# Sheet_1.net
KiCad netlist of a schematic drawn in Altium Designer
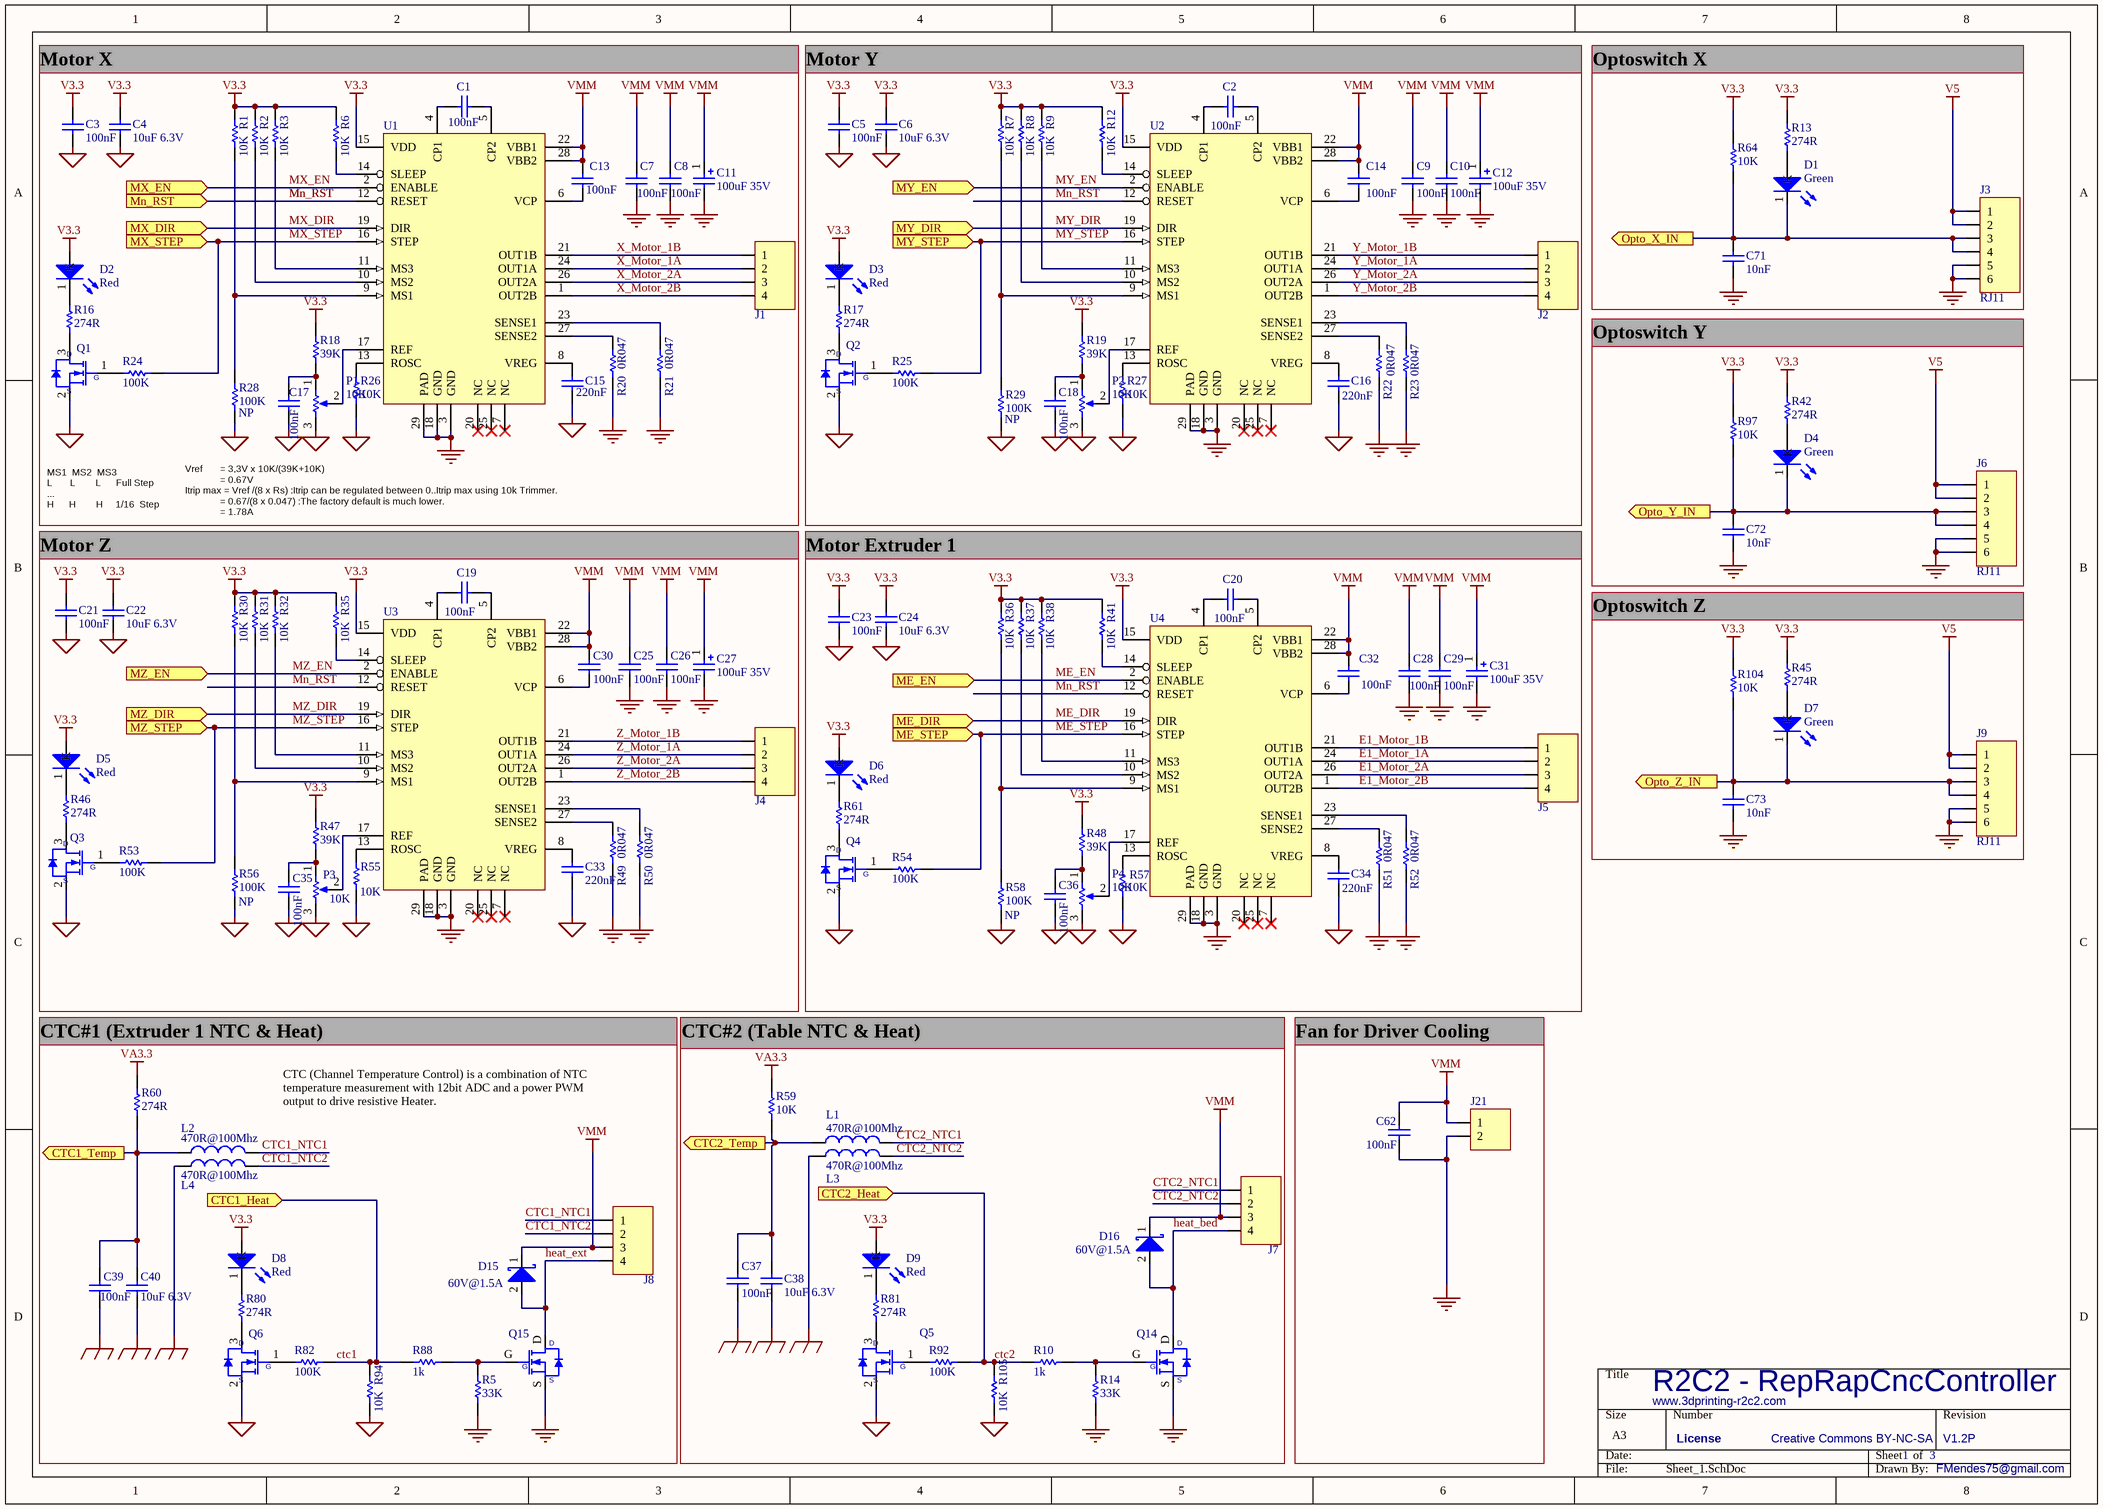
[diagram p0: Sheet_1.SchDoc]

(export (version "E")
  (design (tool "Eeschema 10.0.6"))
  (components
    (comp (ref "C1")
      (value "100nF")
      (footprint "CAPC1608M")
      (description "CAP CER 0.1UF 50V Y5V 0603")
      (fields (field (name "MANUFACTURER") "Yageo"))
      (libsource (lib "HB_DB_Components") (part "Cap Non Pol"))
    )
    (comp (ref "C2")
      (value "100nF")
      (footprint "CAPC1608M")
      (description "CAP CER 0.1UF 50V Y5V 0603")
      (fields (field (name "MANUFACTURER") "Yageo"))
      (libsource (lib "HB_DB_Components") (part "Cap Non Pol"))
    )
    (comp (ref "C3")
      (value "100nF")
      (footprint "CAPC1608M")
      (description "CAP CER 0.1UF 50V Y5V 0603")
      (fields (field (name "MANUFACTURER") "Yageo"))
      (libsource (lib "HB_DB_Components") (part "Cap Non Pol"))
    )
    (comp (ref "C4")
      (value "10uF 6.3V")
      (footprint "CAPC2012M")
      (description "CAP CER 10UF 10V Y5V 0805")
      (fields (field (name "MANUFACTURER") "Yageo"))
      (libsource (lib "HB_DB_Components") (part "Cap Non Pol"))
    )
    (comp (ref "C5")
      (value "100nF")
      (footprint "CAPC1608M")
      (description "CAP CER 0.1UF 50V Y5V 0603")
      (fields (field (name "MANUFACTURER") "Yageo"))
      (libsource (lib "HB_DB_Components") (part "Cap Non Pol"))
    )
    (comp (ref "C6")
      (value "10uF 6.3V")
      (footprint "CAPC2012M")
      (description "CAP CER 10UF 10V Y5V 0805")
      (fields (field (name "MANUFACTURER") "Yageo"))
      (libsource (lib "HB_DB_Components") (part "Cap Non Pol"))
    )
    (comp (ref "C7")
      (value "100nF")
      (footprint "CAPC1608M")
      (description "CAP CER 0.1UF 50V Y5V 0603")
      (fields (field (name "MANUFACTURER") "Yageo"))
      (libsource (lib "HB_DB_Components") (part "Cap Non Pol"))
    )
    (comp (ref "C8")
      (value "100nF")
      (footprint "CAPC1608M")
      (description "CAP CER 0.1UF 50V Y5V 0603")
      (fields (field (name "MANUFACTURER") "Yageo"))
      (libsource (lib "HB_DB_Components") (part "Cap Non Pol"))
    )
    (comp (ref "C9")
      (value "100nF")
      (footprint "CAPC1608M")
      (description "CAP CER 0.1UF 50V Y5V 0603")
      (fields (field (name "MANUFACTURER") "Yageo"))
      (libsource (lib "HB_DB_Components") (part "Cap Non Pol"))
    )
    (comp (ref "C10")
      (value "100nF")
      (footprint "CAPC1608M")
      (description "CAP CER 0.1UF 50V Y5V 0603")
      (fields (field (name "MANUFACTURER") "Yageo"))
      (libsource (lib "HB_DB_Components") (part "Cap Non Pol"))
    )
    (comp (ref "C11")
      (value "100uF 35V")
      (footprint "CAPAE63x63MM")
      (description "CAP ALUM 100UF 35V 20% SMD")
      (fields (field (name "MANUFACTURER") "Panasonic"))
      (libsource (lib "HB_DB_Components") (part "Cap Pol"))
    )
    (comp (ref "C12")
      (value "100uF 35V")
      (footprint "CAPAE63x63MM")
      (description "CAP ALUM 100UF 35V 20% SMD")
      (fields (field (name "MANUFACTURER") "Panasonic"))
      (libsource (lib "HB_DB_Components") (part "Cap Pol"))
    )
    (comp (ref "C13")
      (value "100nF")
      (footprint "CAPC1608M")
      (description "CAP CER 0.1UF 50V Y5V 0603")
      (fields (field (name "MANUFACTURER") "Yageo"))
      (libsource (lib "HB_DB_Components") (part "Cap Non Pol"))
    )
    (comp (ref "C14")
      (value "100nF")
      (footprint "CAPC1608M")
      (description "CAP CER 0.1UF 50V Y5V 0603")
      (fields (field (name "MANUFACTURER") "Yageo"))
      (libsource (lib "HB_DB_Components") (part "Cap Non Pol"))
    )
    (comp (ref "C15")
      (value "220nF")
      (footprint "CAPC1608M")
      (description "CAP CER 0.22UF 16V 10% X7R 0603")
      (fields (field (name "MANUFACTURER") "TDK"))
      (libsource (lib "HB_DB_Components") (part "Cap Non Pol"))
    )
    (comp (ref "C16")
      (value "220nF")
      (footprint "CAPC1608M")
      (description "CAP CER 0.22UF 16V 10% X7R 0603")
      (fields (field (name "MANUFACTURER") "TDK"))
      (libsource (lib "HB_DB_Components") (part "Cap Non Pol"))
    )
    (comp (ref "C17")
      (value "100nF")
      (footprint "CAPC1608M")
      (description "CAP CER 0.1UF 50V Y5V 0603")
      (fields (field (name "MANUFACTURER") "Yageo"))
      (libsource (lib "HB_DB_Components") (part "Cap Non Pol"))
    )
    (comp (ref "C18")
      (value "100nF")
      (footprint "CAPC1608M")
      (description "CAP CER 0.1UF 50V Y5V 0603")
      (fields (field (name "MANUFACTURER") "Yageo"))
      (libsource (lib "HB_DB_Components") (part "Cap Non Pol"))
    )
    (comp (ref "C19")
      (value "100nF")
      (footprint "CAPC1608M")
      (description "CAP CER 0.1UF 50V Y5V 0603")
      (fields (field (name "MANUFACTURER") "Yageo"))
      (libsource (lib "HB_DB_Components") (part "Cap Non Pol"))
    )
    (comp (ref "C20")
      (value "100nF")
      (footprint "CAPC1608M")
      (description "CAP CER 0.1UF 50V Y5V 0603")
      (fields (field (name "MANUFACTURER") "Yageo"))
      (libsource (lib "HB_DB_Components") (part "Cap Non Pol"))
    )
    (comp (ref "C21")
      (value "100nF")
      (footprint "CAPC1608M")
      (description "CAP CER 0.1UF 50V Y5V 0603")
      (fields (field (name "MANUFACTURER") "Yageo"))
      (libsource (lib "HB_DB_Components") (part "Cap Non Pol"))
    )
    (comp (ref "C22")
      (value "10uF 6.3V")
      (footprint "CAPC2012M")
      (description "CAP CER 10UF 10V Y5V 0805")
      (fields (field (name "MANUFACTURER") "Yageo"))
      (libsource (lib "HB_DB_Components") (part "Cap Non Pol"))
    )
    (comp (ref "C23")
      (value "100nF")
      (footprint "CAPC1608M")
      (description "CAP CER 0.1UF 50V Y5V 0603")
      (fields (field (name "MANUFACTURER") "Yageo"))
      (libsource (lib "HB_DB_Components") (part "Cap Non Pol"))
    )
    (comp (ref "C24")
      (value "10uF 6.3V")
      (footprint "CAPC2012M")
      (description "CAP CER 10UF 10V Y5V 0805")
      (fields (field (name "MANUFACTURER") "Yageo"))
      (libsource (lib "HB_DB_Components") (part "Cap Non Pol"))
    )
    (comp (ref "C25")
      (value "100nF")
      (footprint "CAPC1608M")
      (description "CAP CER 0.1UF 50V Y5V 0603")
      (fields (field (name "MANUFACTURER") "Yageo"))
      (libsource (lib "HB_DB_Components") (part "Cap Non Pol"))
    )
    (comp (ref "C26")
      (value "100nF")
      (footprint "CAPC1608M")
      (description "CAP CER 0.1UF 50V Y5V 0603")
      (fields (field (name "MANUFACTURER") "Yageo"))
      (libsource (lib "HB_DB_Components") (part "Cap Non Pol"))
    )
    (comp (ref "C27")
      (value "100uF 35V")
      (footprint "CAPAE63x63MM")
      (description "CAP ALUM 100UF 35V 20% SMD")
      (fields (field (name "MANUFACTURER") "Panasonic"))
      (libsource (lib "HB_DB_Components") (part "Cap Pol"))
    )
    (comp (ref "C28")
      (value "100nF")
      (footprint "CAPC1608M")
      (description "CAP CER 0.1UF 50V Y5V 0603")
      (fields (field (name "MANUFACTURER") "Yageo"))
      (libsource (lib "HB_DB_Components") (part "Cap Non Pol"))
    )
    (comp (ref "C29")
      (value "100nF")
      (footprint "CAPC1608M")
      (description "CAP CER 0.1UF 50V Y5V 0603")
      (fields (field (name "MANUFACTURER") "Yageo"))
      (libsource (lib "HB_DB_Components") (part "Cap Non Pol"))
    )
    (comp (ref "C30")
      (value "100nF")
      (footprint "CAPC1608M")
      (description "CAP CER 0.1UF 50V Y5V 0603")
      (fields (field (name "MANUFACTURER") "Yageo"))
      (libsource (lib "HB_DB_Components") (part "Cap Non Pol"))
    )
    (comp (ref "C31")
      (value "100uF 35V")
      (footprint "CAPAE63x63MM")
      (description "CAP ALUM 100UF 35V 20% SMD")
      (fields (field (name "MANUFACTURER") "Panasonic"))
      (libsource (lib "HB_DB_Components") (part "Cap Pol"))
    )
    (comp (ref "C32")
      (value "100nF")
      (footprint "CAPC1608M")
      (description "CAP CER 0.1UF 50V Y5V 0603")
      (fields (field (name "MANUFACTURER") "Yageo"))
      (libsource (lib "HB_DB_Components") (part "Cap Non Pol"))
    )
    (comp (ref "C33")
      (value "220nF")
      (footprint "CAPC1608M")
      (description "CAP CER 0.22UF 16V 10% X7R 0603")
      (fields (field (name "MANUFACTURER") "TDK"))
      (libsource (lib "HB_DB_Components") (part "Cap Non Pol"))
    )
    (comp (ref "C34")
      (value "220nF")
      (footprint "CAPC1608M")
      (description "CAP CER 0.22UF 16V 10% X7R 0603")
      (fields (field (name "MANUFACTURER") "TDK"))
      (libsource (lib "HB_DB_Components") (part "Cap Non Pol"))
    )
    (comp (ref "C35")
      (value "100nF")
      (footprint "CAPC1608M")
      (description "CAP CER 0.1UF 50V Y5V 0603")
      (fields (field (name "MANUFACTURER") "Yageo"))
      (libsource (lib "HB_DB_Components") (part "Cap Non Pol"))
    )
    (comp (ref "C36")
      (value "100nF")
      (footprint "CAPC1608M")
      (description "CAP CER 0.1UF 50V Y5V 0603")
      (fields (field (name "MANUFACTURER") "Yageo"))
      (libsource (lib "HB_DB_Components") (part "Cap Non Pol"))
    )
    (comp (ref "C37")
      (value "100nF")
      (footprint "CAPC1608M")
      (description "CAP CER 0.1UF 50V Y5V 0603")
      (fields (field (name "MANUFACTURER") "Yageo"))
      (libsource (lib "HB_DB_Components") (part "Cap Non Pol"))
    )
    (comp (ref "C38")
      (value "10uF 6.3V")
      (footprint "CAPC2012M")
      (description "CAP CER 10UF 10V Y5V 0805")
      (fields (field (name "MANUFACTURER") "Yageo"))
      (libsource (lib "HB_DB_Components") (part "Cap Non Pol"))
    )
    (comp (ref "C39")
      (value "100nF")
      (footprint "CAPC1608M")
      (description "CAP CER 0.1UF 50V Y5V 0603")
      (fields (field (name "MANUFACTURER") "Yageo"))
      (libsource (lib "HB_DB_Components") (part "Cap Non Pol"))
    )
    (comp (ref "C40")
      (value "10uF 6.3V")
      (footprint "CAPC2012M")
      (description "CAP CER 10UF 10V Y5V 0805")
      (fields (field (name "MANUFACTURER") "Yageo"))
      (libsource (lib "HB_DB_Components") (part "Cap Non Pol"))
    )
    (comp (ref "C62")
      (value "100nF")
      (footprint "CAPC1608M")
      (description "CAP CER 0.1UF 50V Y5V 0603")
      (fields (field (name "MANUFACTURER") "Yageo"))
      (libsource (lib "HB_DB_Components") (part "Cap Non Pol"))
    )
    (comp (ref "C71")
      (value "10nF")
      (footprint "CAPC1608M")
      (description "CAP CER 10000PF 50V 10% X7R 0603")
      (fields (field (name "MANUFACTURER") "TDK"))
      (libsource (lib "HB_DB_Components") (part "Cap Non Pol"))
    )
    (comp (ref "C72")
      (value "10nF")
      (footprint "CAPC1608M")
      (description "CAP CER 10000PF 50V 10% X7R 0603")
      (fields (field (name "MANUFACTURER") "TDK"))
      (libsource (lib "HB_DB_Components") (part "Cap Non Pol"))
    )
    (comp (ref "C73")
      (value "10nF")
      (footprint "CAPC1608M")
      (description "CAP CER 10000PF 50V 10% X7R 0603")
      (fields (field (name "MANUFACTURER") "TDK"))
      (libsource (lib "HB_DB_Components") (part "Cap Non Pol"))
    )
    (comp (ref "D1")
      (value "Green")
      (footprint "LEDM_3216X12M")
      (description "LED CHIPLED 570NM GREEN 1206 SMD")
      (fields (field (name "MANUFACTURER") "OSRAM"))
      (libsource (lib "altium-import") (part "root_3_LED_"))
    )
    (comp (ref "D2")
      (value "Red")
      (footprint "LEDM_3216X12M")
      (description "LED CHIPLED 645NM RED DIFF 1206")
      (fields (field (name "MANUFACTURER") "OSRAM"))
      (libsource (lib "HB_DB_Components") (part "LED"))
    )
    (comp (ref "D3")
      (value "Red")
      (footprint "LEDM_3216X12M")
      (description "LED CHIPLED 645NM RED DIFF 1206")
      (fields (field (name "MANUFACTURER") "OSRAM"))
      (libsource (lib "HB_DB_Components") (part "LED"))
    )
    (comp (ref "D4")
      (value "Green")
      (footprint "LEDM_3216X12M")
      (description "LED CHIPLED 570NM GREEN 1206 SMD")
      (fields (field (name "MANUFACTURER") "OSRAM"))
      (libsource (lib "altium-import") (part "root_3_LED_"))
    )
    (comp (ref "D5")
      (value "Red")
      (footprint "LEDM_3216X12M")
      (description "LED CHIPLED 645NM RED DIFF 1206")
      (fields (field (name "MANUFACTURER") "OSRAM"))
      (libsource (lib "HB_DB_Components") (part "LED"))
    )
    (comp (ref "D6")
      (value "Red")
      (footprint "LEDM_3216X12M")
      (description "LED CHIPLED 645NM RED DIFF 1206")
      (fields (field (name "MANUFACTURER") "OSRAM"))
      (libsource (lib "HB_DB_Components") (part "LED"))
    )
    (comp (ref "D7")
      (value "Green")
      (footprint "LEDM_3216X12M")
      (description "LED CHIPLED 570NM GREEN 1206 SMD")
      (fields (field (name "MANUFACTURER") "OSRAM"))
      (libsource (lib "altium-import") (part "root_3_LED_"))
    )
    (comp (ref "D8")
      (value "Red")
      (footprint "LEDM_3216X12M")
      (description "LED CHIPLED 645NM RED DIFF 1206")
      (fields (field (name "MANUFACTURER") "OSRAM"))
      (libsource (lib "HB_DB_Components") (part "LED"))
    )
    (comp (ref "D9")
      (value "Red")
      (footprint "LEDM_3216X12M")
      (description "LED CHIPLED 645NM RED DIFF 1206")
      (fields (field (name "MANUFACTURER") "OSRAM"))
      (libsource (lib "HB_DB_Components") (part "LED"))
    )
    (comp (ref "D15")
      (value "60V@1.5A")
      (footprint "SMA")
      (description "DIODE SCHOTTKY 60V 2.1A DO214AC")
      (fields (field (name "MANUFACTURER") "VISHAY"))
      (libsource (lib "HB_DB_Components") (part "D Schottky"))
    )
    (comp (ref "D16")
      (value "60V@1.5A")
      (footprint "SMA")
      (description "DIODE SCHOTTKY 60V 2.1A DO214AC")
      (fields (field (name "MANUFACTURER") "VISHAY"))
      (libsource (lib "HB_DB_Components") (part "D Schottky"))
    )
    (comp (ref "J1")
      (value "~")
      (footprint "TE_SCREW_1X4")
      (description "Con 4")
      (fields (field (name "MANUFACTURER") "TE"))
      (libsource (lib "HB_DB_Components") (part "Con 4"))
    )
    (comp (ref "J2")
      (value "~")
      (footprint "TE_SCREW_1X4")
      (description "Con 4")
      (fields (field (name "MANUFACTURER") "TE"))
      (libsource (lib "HB_DB_Components") (part "Con 4"))
    )
    (comp (ref "J3")
      (value "RJ11")
      (footprint "MOLEX_95022-2667")
      (description "CONN MOD JACK R/A 6P4C")
      (fields (field (name "MANUFACTURER") "Stewart Connector"))
      (libsource (lib "HB_DB_Components") (part "Con 6"))
    )
    (comp (ref "J4")
      (value "~")
      (footprint "TE_SCREW_1X4")
      (description "Con 4")
      (fields (field (name "MANUFACTURER") "TE"))
      (libsource (lib "HB_DB_Components") (part "Con 4"))
    )
    (comp (ref "J5")
      (value "~")
      (footprint "TE_SCREW_1X4")
      (description "Con 4")
      (fields (field (name "MANUFACTURER") "TE"))
      (libsource (lib "HB_DB_Components") (part "Con 4"))
    )
    (comp (ref "J6")
      (value "RJ11")
      (footprint "MOLEX_95022-2667")
      (description "CONN MOD JACK R/A 6P4C")
      (fields (field (name "MANUFACTURER") "Stewart Connector"))
      (libsource (lib "HB_DB_Components") (part "Con 6"))
    )
    (comp (ref "J7")
      (value "~")
      (footprint "TE_SCREW_282841-4")
      (description "Con 4")
      (fields (field (name "MANUFACTURER") "TE"))
      (libsource (lib "HB_DB_Components") (part "Con 4"))
    )
    (comp (ref "J8")
      (value "~")
      (footprint "TE_SCREW_282841-4")
      (description "Con 4")
      (fields (field (name "MANUFACTURER") "TE"))
      (libsource (lib "HB_DB_Components") (part "Con 4"))
    )
    (comp (ref "J9")
      (value "RJ11")
      (footprint "MOLEX_95022-2667")
      (description "CONN MOD JACK R/A 6P4C")
      (fields (field (name "MANUFACTURER") "Stewart Connector"))
      (libsource (lib "HB_DB_Components") (part "Con 6"))
    )
    (comp (ref "J21")
      (value "-")
      (footprint "MOLEX_22-29-2021")
      (description "CONN HEADER 2POS .100 VERT GOLD")
      (fields (field (name "MANUFACTURER") "Molex"))
      (libsource (lib "HB_DB_Components") (part "Con 2"))
    )
    (comp (ref "L1")
      (value "470R@100Mhz")
      (footprint "INDC1608M")
      (description "FERRITE CHIP 470 OHM 1000MA 0603")
      (fields (field (name "MANUFACTURER") "MURATA"))
      (libsource (lib "HB_DB_Components") (part "Ind"))
    )
    (comp (ref "L2")
      (value "470R@100Mhz")
      (footprint "INDC1608M")
      (description "FERRITE CHIP 470 OHM 1000MA 0603")
      (fields (field (name "MANUFACTURER") "MURATA"))
      (libsource (lib "HB_DB_Components") (part "Ind"))
    )
    (comp (ref "L3")
      (value "470R@100Mhz")
      (footprint "INDC1608M")
      (description "FERRITE CHIP 470 OHM 1000MA 0603")
      (fields (field (name "MANUFACTURER") "MURATA"))
      (libsource (lib "HB_DB_Components") (part "Ind"))
    )
    (comp (ref "L4")
      (value "470R@100Mhz")
      (footprint "INDC1608M")
      (description "FERRITE CHIP 470 OHM 1000MA 0603")
      (fields (field (name "MANUFACTURER") "MURATA"))
      (libsource (lib "HB_DB_Components") (part "Ind"))
    )
    (comp (ref "P1")
      (value "10K")
      (footprint "Trimmer_14")
      (description "TRIMMER 10K OHM 0.5W TH")
      (fields (field (name "MANUFACTURER") "copal"))
      (libsource (lib "HB_DB_Components") (part "Res Pot"))
    )
    (comp (ref "P2")
      (value "10K")
      (footprint "Trimmer_14")
      (description "TRIMMER 10K OHM 0.5W TH")
      (fields (field (name "MANUFACTURER") "copal"))
      (libsource (lib "HB_DB_Components") (part "Res Pot"))
    )
    (comp (ref "P3")
      (value "10K")
      (footprint "Trimmer_14")
      (description "TRIMMER 10K OHM 0.5W TH")
      (fields (field (name "MANUFACTURER") "copal"))
      (libsource (lib "HB_DB_Components") (part "Res Pot"))
    )
    (comp (ref "P4")
      (value "10K")
      (footprint "Trimmer_14")
      (description "TRIMMER 10K OHM 0.5W TH")
      (fields (field (name "MANUFACTURER") "copal"))
      (libsource (lib "HB_DB_Components") (part "Res Pot"))
    )
    (comp (ref "Q1")
      (value "~")
      (footprint "SOT323-3AM")
      (description "MOSFET N-CH SGL 60V SOT-323")
      (fields (field (name "MANUFACTURER") "NXP"))
      (libsource (lib "") (part "Q MOSFET-N_1"))
    )
    (comp (ref "Q2")
      (value "~")
      (footprint "SOT323-3AM")
      (description "MOSFET N-CH SGL 60V SOT-323")
      (fields (field (name "MANUFACTURER") "NXP"))
      (libsource (lib "") (part "Q MOSFET-N_1"))
    )
    (comp (ref "Q3")
      (value "~")
      (footprint "SOT323-3AM")
      (description "MOSFET N-CH SGL 60V SOT-323")
      (fields (field (name "MANUFACTURER") "NXP"))
      (libsource (lib "") (part "Q MOSFET-N_1"))
    )
    (comp (ref "Q4")
      (value "~")
      (footprint "SOT323-3AM")
      (description "MOSFET N-CH SGL 60V SOT-323")
      (fields (field (name "MANUFACTURER") "NXP"))
      (libsource (lib "") (part "Q MOSFET-N_1"))
    )
    (comp (ref "Q5")
      (value "~")
      (footprint "SOT323-3AM")
      (description "MOSFET N-CH SGL 60V SOT-323")
      (fields (field (name "MANUFACTURER") "NXP"))
      (libsource (lib "") (part "Q MOSFET-N_1"))
    )
    (comp (ref "Q6")
      (value "~")
      (footprint "SOT323-3AM")
      (description "MOSFET N-CH SGL 60V SOT-323")
      (fields (field (name "MANUFACTURER") "NXP"))
      (libsource (lib "") (part "Q MOSFET-N_1"))
    )
    (comp (ref "Q14")
      (value "~")
      (footprint "SuperSOP8_csd17301")
      (description "MOSFET N-CH 30V 28A 8SON")
      (fields (field (name "MANUFACTURER") "Texas Instruments"))
      (libsource (lib "HB_DB_Components") (part "Q MOSFET-N"))
    )
    (comp (ref "Q15")
      (value "~")
      (footprint "SuperSOP8_csd17301")
      (description "MOSFET N-CH 30V 28A 8SON")
      (fields (field (name "MANUFACTURER") "Texas Instruments"))
      (libsource (lib "HB_DB_Components") (part "Q MOSFET-N"))
    )
    (comp (ref "R1")
      (value "10K")
      (footprint "RESC1608M")
      (description "RES 10K OHM 1/10W 5% 0603 SMD")
      (fields (field (name "MANUFACTURER") "Yageo"))
      (libsource (lib "HB_DB_Components") (part "Res"))
    )
    (comp (ref "R2")
      (value "10K")
      (footprint "RESC1608M")
      (description "RES 10K OHM 1/10W 5% 0603 SMD")
      (fields (field (name "MANUFACTURER") "Yageo"))
      (libsource (lib "HB_DB_Components") (part "Res"))
    )
    (comp (ref "R3")
      (value "10K")
      (footprint "RESC1608M")
      (description "RES 10K OHM 1/10W 5% 0603 SMD")
      (fields (field (name "MANUFACTURER") "Yageo"))
      (libsource (lib "HB_DB_Components") (part "Res"))
    )
    (comp (ref "R5")
      (value "33K")
      (footprint "RESC1608M")
      (description "RES 33K OHM 1/10W 1% 0603")
      (fields (field (name "MANUFACTURER") "Stackpole Electronics Inc"))
      (libsource (lib "HB_DB_Components") (part "Res"))
    )
    (comp (ref "R6")
      (value "10K")
      (footprint "RESC1608M")
      (description "RES 10K OHM 1/10W 5% 0603 SMD")
      (fields (field (name "MANUFACTURER") "Yageo"))
      (libsource (lib "HB_DB_Components") (part "Res"))
    )
    (comp (ref "R7")
      (value "10K")
      (footprint "RESC1608M")
      (description "RES 10K OHM 1/10W 5% 0603 SMD")
      (fields (field (name "MANUFACTURER") "Yageo"))
      (libsource (lib "HB_DB_Components") (part "Res"))
    )
    (comp (ref "R8")
      (value "10K")
      (footprint "RESC1608M")
      (description "RES 10K OHM 1/10W 5% 0603 SMD")
      (fields (field (name "MANUFACTURER") "Yageo"))
      (libsource (lib "HB_DB_Components") (part "Res"))
    )
    (comp (ref "R9")
      (value "10K")
      (footprint "RESC1608M")
      (description "RES 10K OHM 1/10W 5% 0603 SMD")
      (fields (field (name "MANUFACTURER") "Yageo"))
      (libsource (lib "HB_DB_Components") (part "Res"))
    )
    (comp (ref "R10")
      (value "1k")
      (footprint "RESC1608M")
      (description "RES 1K OHM 1/10W 5% 0603")
      (fields (field (name "MANUFACTURER") "Stackpole Electronics Inc"))
      (libsource (lib "HB_DB_Components") (part "Res"))
    )
    (comp (ref "R12")
      (value "10K")
      (footprint "RESC1608M")
      (description "RES 10K OHM 1/10W 5% 0603 SMD")
      (fields (field (name "MANUFACTURER") "Yageo"))
      (libsource (lib "HB_DB_Components") (part "Res"))
    )
    (comp (ref "R13")
      (value "274R")
      (footprint "RESC1608M")
      (description "RES 274 OHM 1/10W 1% 0603")
      (fields (field (name "MANUFACTURER") "Stackpole Electronics Inc"))
      (libsource (lib "HB_DB_Components") (part "Res"))
    )
    (comp (ref "R14")
      (value "33K")
      (footprint "RESC1608M")
      (description "RES 33K OHM 1/10W 1% 0603")
      (fields (field (name "MANUFACTURER") "Stackpole Electronics Inc"))
      (libsource (lib "HB_DB_Components") (part "Res"))
    )
    (comp (ref "R16")
      (value "274R")
      (footprint "RESC1608M")
      (description "RES 274 OHM 1/10W 1% 0603")
      (fields (field (name "MANUFACTURER") "Stackpole Electronics Inc"))
      (libsource (lib "HB_DB_Components") (part "Res"))
    )
    (comp (ref "R17")
      (value "274R")
      (footprint "RESC1608M")
      (description "RES 274 OHM 1/10W 1% 0603")
      (fields (field (name "MANUFACTURER") "Stackpole Electronics Inc"))
      (libsource (lib "HB_DB_Components") (part "Res"))
    )
    (comp (ref "R18")
      (value "39K")
      (footprint "RESC1608M")
      (description "RES 39K OHM 1/10W 1% 0603")
      (fields (field (name "MANUFACTURER") "Stackpole Electronics Inc"))
      (libsource (lib "HB_DB_Components") (part "Res"))
    )
    (comp (ref "R19")
      (value "39K")
      (footprint "RESC1608M")
      (description "RES 39K OHM 1/10W 1% 0603")
      (fields (field (name "MANUFACTURER") "Stackpole Electronics Inc"))
      (libsource (lib "HB_DB_Components") (part "Res"))
    )
    (comp (ref "R20")
      (value "0R047")
      (footprint "RESC3216M")
      (description "RES .047 OHM 1/2W 1% 1206 SMD")
      (fields (field (name "MANUFACTURER") "Ohmite"))
      (libsource (lib "HB_DB_Components") (part "Res"))
    )
    (comp (ref "R21")
      (value "0R047")
      (footprint "RESC3216M")
      (description "RES .047 OHM 1/2W 1% 1206 SMD")
      (fields (field (name "MANUFACTURER") "Ohmite"))
      (libsource (lib "HB_DB_Components") (part "Res"))
    )
    (comp (ref "R22")
      (value "0R047")
      (footprint "RESC3216M")
      (description "RES .047 OHM 1/2W 1% 1206 SMD")
      (fields (field (name "MANUFACTURER") "Ohmite"))
      (libsource (lib "HB_DB_Components") (part "Res"))
    )
    (comp (ref "R23")
      (value "0R047")
      (footprint "RESC3216M")
      (description "RES .047 OHM 1/2W 1% 1206 SMD")
      (fields (field (name "MANUFACTURER") "Ohmite"))
      (libsource (lib "HB_DB_Components") (part "Res"))
    )
    (comp (ref "R24")
      (value "100K")
      (footprint "RESC1608M")
      (description "RES 100K OHM 1/10W 5% 0603 SMD")
      (fields (field (name "MANUFACTURER") "Yageo"))
      (libsource (lib "HB_DB_Components") (part "Res"))
    )
    (comp (ref "R25")
      (value "100K")
      (footprint "RESC1608M")
      (description "RES 100K OHM 1/10W 5% 0603 SMD")
      (fields (field (name "MANUFACTURER") "Yageo"))
      (libsource (lib "HB_DB_Components") (part "Res"))
    )
    (comp (ref "R26")
      (value "10K")
      (footprint "RESC1608M")
      (description "RES 10K OHM 1/10W 5% 0603 SMD")
      (fields (field (name "MANUFACTURER") "Yageo"))
      (libsource (lib "HB_DB_Components") (part "Res"))
    )
    (comp (ref "R27")
      (value "10K")
      (footprint "RESC1608M")
      (description "RES 10K OHM 1/10W 5% 0603 SMD")
      (fields (field (name "MANUFACTURER") "Yageo"))
      (libsource (lib "HB_DB_Components") (part "Res"))
    )
    (comp (ref "R28")
      (value "100K")
      (footprint "RESC1608M")
      (description "RES 100K OHM 1/10W 5% 0603 SMD")
      (fields (field (name "MANUFACTURER") "Yageo") (field (name "POPULATE") "NP"))
      (libsource (lib "HB_DB_Components") (part "Res"))
    )
    (comp (ref "R29")
      (value "100K")
      (footprint "RESC1608M")
      (description "RES 100K OHM 1/10W 5% 0603 SMD")
      (fields (field (name "MANUFACTURER") "Yageo") (field (name "POPULATE") "NP"))
      (libsource (lib "HB_DB_Components") (part "Res"))
    )
    (comp (ref "R30")
      (value "10K")
      (footprint "RESC1608M")
      (description "RES 10K OHM 1/10W 5% 0603 SMD")
      (fields (field (name "MANUFACTURER") "Yageo"))
      (libsource (lib "HB_DB_Components") (part "Res"))
    )
    (comp (ref "R31")
      (value "10K")
      (footprint "RESC1608M")
      (description "RES 10K OHM 1/10W 5% 0603 SMD")
      (fields (field (name "MANUFACTURER") "Yageo"))
      (libsource (lib "HB_DB_Components") (part "Res"))
    )
    (comp (ref "R32")
      (value "10K")
      (footprint "RESC1608M")
      (description "RES 10K OHM 1/10W 5% 0603 SMD")
      (fields (field (name "MANUFACTURER") "Yageo"))
      (libsource (lib "HB_DB_Components") (part "Res"))
    )
    (comp (ref "R35")
      (value "10K")
      (footprint "RESC1608M")
      (description "RES 10K OHM 1/10W 5% 0603 SMD")
      (fields (field (name "MANUFACTURER") "Yageo"))
      (libsource (lib "HB_DB_Components") (part "Res"))
    )
    (comp (ref "R36")
      (value "10K")
      (footprint "RESC1608M")
      (description "RES 10K OHM 1/10W 5% 0603 SMD")
      (fields (field (name "MANUFACTURER") "Yageo"))
      (libsource (lib "HB_DB_Components") (part "Res"))
    )
    (comp (ref "R37")
      (value "10K")
      (footprint "RESC1608M")
      (description "RES 10K OHM 1/10W 5% 0603 SMD")
      (fields (field (name "MANUFACTURER") "Yageo"))
      (libsource (lib "HB_DB_Components") (part "Res"))
    )
    (comp (ref "R38")
      (value "10K")
      (footprint "RESC1608M")
      (description "RES 10K OHM 1/10W 5% 0603 SMD")
      (fields (field (name "MANUFACTURER") "Yageo"))
      (libsource (lib "HB_DB_Components") (part "Res"))
    )
    (comp (ref "R41")
      (value "10K")
      (footprint "RESC1608M")
      (description "RES 10K OHM 1/10W 5% 0603 SMD")
      (fields (field (name "MANUFACTURER") "Yageo"))
      (libsource (lib "HB_DB_Components") (part "Res"))
    )
    (comp (ref "R42")
      (value "274R")
      (footprint "RESC1608M")
      (description "RES 274 OHM 1/10W 1% 0603")
      (fields (field (name "MANUFACTURER") "Stackpole Electronics Inc"))
      (libsource (lib "HB_DB_Components") (part "Res"))
    )
    (comp (ref "R45")
      (value "274R")
      (footprint "RESC1608M")
      (description "RES 274 OHM 1/10W 1% 0603")
      (fields (field (name "MANUFACTURER") "Stackpole Electronics Inc"))
      (libsource (lib "HB_DB_Components") (part "Res"))
    )
    (comp (ref "R46")
      (value "274R")
      (footprint "RESC1608M")
      (description "RES 274 OHM 1/10W 1% 0603")
      (fields (field (name "MANUFACTURER") "Stackpole Electronics Inc"))
      (libsource (lib "HB_DB_Components") (part "Res"))
    )
    (comp (ref "R47")
      (value "39K")
      (footprint "RESC1608M")
      (description "RES 39K OHM 1/10W 1% 0603")
      (fields (field (name "MANUFACTURER") "Stackpole Electronics Inc"))
      (libsource (lib "HB_DB_Components") (part "Res"))
    )
    (comp (ref "R48")
      (value "39K")
      (footprint "RESC1608M")
      (description "RES 39K OHM 1/10W 1% 0603")
      (fields (field (name "MANUFACTURER") "Stackpole Electronics Inc"))
      (libsource (lib "HB_DB_Components") (part "Res"))
    )
    (comp (ref "R49")
      (value "0R047")
      (footprint "RESC3216M")
      (description "RES .047 OHM 1/2W 1% 1206 SMD")
      (fields (field (name "MANUFACTURER") "Ohmite"))
      (libsource (lib "HB_DB_Components") (part "Res"))
    )
    (comp (ref "R50")
      (value "0R047")
      (footprint "RESC3216M")
      (description "RES .047 OHM 1/2W 1% 1206 SMD")
      (fields (field (name "MANUFACTURER") "Ohmite"))
      (libsource (lib "HB_DB_Components") (part "Res"))
    )
    (comp (ref "R51")
      (value "0R047")
      (footprint "RESC3216M")
      (description "RES .047 OHM 1/2W 1% 1206 SMD")
      (fields (field (name "MANUFACTURER") "Ohmite"))
      (libsource (lib "HB_DB_Components") (part "Res"))
    )
    (comp (ref "R52")
      (value "0R047")
      (footprint "RESC3216M")
      (description "RES .047 OHM 1/2W 1% 1206 SMD")
      (fields (field (name "MANUFACTURER") "Ohmite"))
      (libsource (lib "HB_DB_Components") (part "Res"))
    )
    (comp (ref "R53")
      (value "100K")
      (footprint "RESC1608M")
      (description "RES 100K OHM 1/10W 5% 0603 SMD")
      (fields (field (name "MANUFACTURER") "Yageo"))
      (libsource (lib "HB_DB_Components") (part "Res"))
    )
    (comp (ref "R54")
      (value "100K")
      (footprint "RESC1608M")
      (description "RES 100K OHM 1/10W 5% 0603 SMD")
      (fields (field (name "MANUFACTURER") "Yageo"))
      (libsource (lib "HB_DB_Components") (part "Res"))
    )
    (comp (ref "R55")
      (value "10K")
      (footprint "RESC1608M")
      (description "RES 10K OHM 1/10W 5% 0603 SMD")
      (fields (field (name "MANUFACTURER") "Yageo"))
      (libsource (lib "HB_DB_Components") (part "Res"))
    )
    (comp (ref "R56")
      (value "100K")
      (footprint "RESC1608M")
      (description "RES 100K OHM 1/10W 5% 0603 SMD")
      (fields (field (name "MANUFACTURER") "Yageo") (field (name "POPULATE") "NP"))
      (libsource (lib "HB_DB_Components") (part "Res"))
    )
    (comp (ref "R57")
      (value "10K")
      (footprint "RESC1608M")
      (description "RES 10K OHM 1/10W 5% 0603 SMD")
      (fields (field (name "MANUFACTURER") "Yageo"))
      (libsource (lib "HB_DB_Components") (part "Res"))
    )
    (comp (ref "R58")
      (value "100K")
      (footprint "RESC1608M")
      (description "RES 100K OHM 1/10W 5% 0603 SMD")
      (fields (field (name "MANUFACTURER") "Yageo") (field (name "POPULATE") "NP"))
      (libsource (lib "HB_DB_Components") (part "Res"))
    )
    (comp (ref "R59")
      (value "10K")
      (footprint "RESC1608M")
      (description "RES 10K OHM 1/10W 5% 0603 SMD")
      (fields (field (name "MANUFACTURER") "Yageo"))
      (libsource (lib "HB_DB_Components") (part "Res"))
    )
    (comp (ref "R60")
      (value "274R")
      (footprint "RESC1608M")
      (description "RES 274 OHM 1/10W 1% 0603")
      (fields (field (name "MANUFACTURER") "Stackpole Electronics Inc"))
      (libsource (lib "HB_DB_Components") (part "Res"))
    )
    (comp (ref "R61")
      (value "274R")
      (footprint "RESC1608M")
      (description "RES 274 OHM 1/10W 1% 0603")
      (fields (field (name "MANUFACTURER") "Stackpole Electronics Inc"))
      (libsource (lib "HB_DB_Components") (part "Res"))
    )
    (comp (ref "R64")
      (value "10K")
      (footprint "RESC1608M")
      (description "RES 10K OHM 1/10W 5% 0603 SMD")
      (fields (field (name "MANUFACTURER") "Yageo"))
      (libsource (lib "HB_DB_Components") (part "Res"))
    )
    (comp (ref "R80")
      (value "274R")
      (footprint "RESC1608M")
      (description "RES 274 OHM 1/10W 1% 0603")
      (fields (field (name "MANUFACTURER") "Stackpole Electronics Inc"))
      (libsource (lib "HB_DB_Components") (part "Res"))
    )
    (comp (ref "R81")
      (value "274R")
      (footprint "RESC1608M")
      (description "RES 274 OHM 1/10W 1% 0603")
      (fields (field (name "MANUFACTURER") "Stackpole Electronics Inc"))
      (libsource (lib "HB_DB_Components") (part "Res"))
    )
    (comp (ref "R82")
      (value "100K")
      (footprint "RESC1608M")
      (description "RES 100K OHM 1/10W 5% 0603 SMD")
      (fields (field (name "MANUFACTURER") "Yageo"))
      (libsource (lib "HB_DB_Components") (part "Res"))
    )
    (comp (ref "R88")
      (value "1k")
      (footprint "RESC1608M")
      (description "RES 1K OHM 1/10W 5% 0603")
      (fields (field (name "MANUFACTURER") "Stackpole Electronics Inc"))
      (libsource (lib "HB_DB_Components") (part "Res"))
    )
    (comp (ref "R92")
      (value "100K")
      (footprint "RESC1608M")
      (description "RES 100K OHM 1/10W 5% 0603 SMD")
      (fields (field (name "MANUFACTURER") "Yageo"))
      (libsource (lib "HB_DB_Components") (part "Res"))
    )
    (comp (ref "R94")
      (value "10K")
      (footprint "RESC1608M")
      (description "RES 10K OHM 1/10W 5% 0603 SMD")
      (fields (field (name "MANUFACTURER") "Yageo"))
      (libsource (lib "HB_DB_Components") (part "Res"))
    )
    (comp (ref "R97")
      (value "10K")
      (footprint "RESC1608M")
      (description "RES 10K OHM 1/10W 5% 0603 SMD")
      (fields (field (name "MANUFACTURER") "Yageo"))
      (libsource (lib "HB_DB_Components") (part "Res"))
    )
    (comp (ref "R104")
      (value "10K")
      (footprint "RESC1608M")
      (description "RES 10K OHM 1/10W 5% 0603 SMD")
      (fields (field (name "MANUFACTURER") "Yageo"))
      (libsource (lib "HB_DB_Components") (part "Res"))
    )
    (comp (ref "R105")
      (value "10K")
      (footprint "RESC1608M")
      (description "RES 10K OHM 1/10W 5% 0603 SMD")
      (fields (field (name "MANUFACTURER") "Yageo"))
      (libsource (lib "HB_DB_Components") (part "Res"))
    )
    (comp (ref "U1")
      (value "~")
      (footprint "QFN50P500X500X100-28M")
      (description "IC MOTOR DRIVER PAR 28QFN")
      (fields (field (name "MANUFACTURER") "Allegro MicroSystems, LLC"))
      (libsource (lib "HB_DB_Components") (part "IC A4988"))
    )
    (comp (ref "U2")
      (value "~")
      (footprint "QFN50P500X500X100-28M")
      (description "IC MOTOR DRIVER PAR 28QFN")
      (fields (field (name "MANUFACTURER") "Allegro MicroSystems, LLC"))
      (libsource (lib "HB_DB_Components") (part "IC A4988"))
    )
    (comp (ref "U3")
      (value "~")
      (footprint "QFN50P500X500X100-28M")
      (description "IC MOTOR DRIVER PAR 28QFN")
      (fields (field (name "MANUFACTURER") "Allegro MicroSystems, LLC"))
      (libsource (lib "HB_DB_Components") (part "IC A4988"))
    )
    (comp (ref "U4")
      (value "~")
      (footprint "QFN50P500X500X100-28M")
      (description "IC MOTOR DRIVER PAR 28QFN")
      (fields (field (name "MANUFACTURER") "Allegro MicroSystems, LLC"))
      (libsource (lib "HB_DB_Components") (part "IC A4988"))
    )
  )
  (nets
    (net (code "1") (name "/CTC1_NTC1") (class "Default")
      (node (ref "J8") (pin "1") (pinfunction "1_1") (pintype "passive"))
      (node (ref "L2") (pin "2") (pinfunction "2_2") (pintype "passive"))
    )
    (net (code "2") (name "/CTC1_NTC2") (class "Default")
      (node (ref "J8") (pin "2") (pinfunction "2_2") (pintype "passive"))
      (node (ref "L4") (pin "2") (pinfunction "2_2") (pintype "passive"))
    )
    (net (code "3") (name "/CTC1_Temp") (class "Default")
      (node (ref "C39") (pin "2") (pinfunction "2_2") (pintype "passive"))
      (node (ref "C40") (pin "2") (pinfunction "2_2") (pintype "passive"))
      (node (ref "L2") (pin "1") (pinfunction "1_1") (pintype "passive"))
      (node (ref "R60") (pin "1") (pinfunction "1_1") (pintype "passive"))
    )
    (net (code "4") (name "/CTC2_NTC1") (class "Default")
      (node (ref "J7") (pin "1") (pinfunction "1_1") (pintype "passive"))
      (node (ref "L1") (pin "2") (pinfunction "2_2") (pintype "passive"))
    )
    (net (code "5") (name "/CTC2_NTC2") (class "Default")
      (node (ref "J7") (pin "2") (pinfunction "2_2") (pintype "passive"))
      (node (ref "L3") (pin "2") (pinfunction "2_2") (pintype "passive"))
    )
    (net (code "6") (name "/CTC2_Temp") (class "Default")
      (node (ref "C37") (pin "2") (pinfunction "2_2") (pintype "passive"))
      (node (ref "C38") (pin "2") (pinfunction "2_2") (pintype "passive"))
      (node (ref "L1") (pin "1") (pinfunction "1_1") (pintype "passive"))
      (node (ref "R59") (pin "1") (pinfunction "1_1") (pintype "passive"))
    )
    (net (code "7") (name "/E1_Motor_1A") (class "Default")
      (node (ref "J5") (pin "2") (pinfunction "2_2") (pintype "passive"))
      (node (ref "U4") (pin "24") (pinfunction "OUT1A_24") (pintype "passive"))
    )
    (net (code "8") (name "/E1_Motor_1B") (class "Default")
      (node (ref "J5") (pin "1") (pinfunction "1_1") (pintype "passive"))
      (node (ref "U4") (pin "21") (pinfunction "OUT1B_21") (pintype "passive"))
    )
    (net (code "9") (name "/E1_Motor_2A") (class "Default")
      (node (ref "J5") (pin "3") (pinfunction "3_3") (pintype "passive"))
      (node (ref "U4") (pin "26") (pinfunction "OUT2A_26") (pintype "passive"))
    )
    (net (code "10") (name "/E1_Motor_2B") (class "Default")
      (node (ref "J5") (pin "4") (pinfunction "4_4") (pintype "passive"))
      (node (ref "U4") (pin "1") (pinfunction "OUT2B_1") (pintype "passive"))
    )
    (net (code "11") (name "/ME_DIR") (class "Default")
      (node (ref "U4") (pin "19") (pinfunction "DIR_19") (pintype "input"))
    )
    (net (code "12") (name "/ME_EN") (class "Default")
      (node (ref "U4") (pin "2") (pinfunction "ENABLE_2") (pintype "passive"))
    )
    (net (code "13") (name "/ME_STEP") (class "Default")
      (node (ref "R54") (pin "2") (pinfunction "2_2") (pintype "passive"))
      (node (ref "U4") (pin "16") (pinfunction "STEP_16") (pintype "input"))
    )
    (net (code "14") (name "/MX_DIR") (class "Default")
      (node (ref "U1") (pin "19") (pinfunction "DIR_19") (pintype "input"))
    )
    (net (code "15") (name "/MX_EN") (class "Default")
      (node (ref "U1") (pin "2") (pinfunction "ENABLE_2") (pintype "passive"))
    )
    (net (code "16") (name "/MX_STEP") (class "Default")
      (node (ref "R24") (pin "2") (pinfunction "2_2") (pintype "passive"))
      (node (ref "U1") (pin "16") (pinfunction "STEP_16") (pintype "input"))
    )
    (net (code "17") (name "/MY_DIR") (class "Default")
      (node (ref "U2") (pin "19") (pinfunction "DIR_19") (pintype "input"))
    )
    (net (code "18") (name "/MY_EN") (class "Default")
      (node (ref "U2") (pin "2") (pinfunction "ENABLE_2") (pintype "passive"))
    )
    (net (code "19") (name "/MY_STEP") (class "Default")
      (node (ref "R25") (pin "2") (pinfunction "2_2") (pintype "passive"))
      (node (ref "U2") (pin "16") (pinfunction "STEP_16") (pintype "input"))
    )
    (net (code "20") (name "/MZ_DIR") (class "Default")
      (node (ref "U3") (pin "19") (pinfunction "DIR_19") (pintype "input"))
    )
    (net (code "21") (name "/MZ_EN") (class "Default")
      (node (ref "U3") (pin "2") (pinfunction "ENABLE_2") (pintype "passive"))
    )
    (net (code "22") (name "/MZ_STEP") (class "Default")
      (node (ref "R53") (pin "2") (pinfunction "2_2") (pintype "passive"))
      (node (ref "U3") (pin "16") (pinfunction "STEP_16") (pintype "input"))
    )
    (net (code "23") (name "/Mn_RST") (class "Default")
      (node (ref "U1") (pin "12") (pinfunction "RESET_12") (pintype "passive"))
      (node (ref "U2") (pin "12") (pinfunction "RESET_12") (pintype "passive"))
      (node (ref "U3") (pin "12") (pinfunction "RESET_12") (pintype "passive"))
      (node (ref "U4") (pin "12") (pinfunction "RESET_12") (pintype "passive"))
    )
    (net (code "24") (name "/Opto_X_IN") (class "Default")
      (node (ref "C71") (pin "1") (pinfunction "1_1") (pintype "passive"))
      (node (ref "D1") (pin "1") (pinfunction "K_1") (pintype "passive"))
      (node (ref "J3") (pin "3") (pinfunction "3_3") (pintype "passive"))
      (node (ref "J3") (pin "4") (pinfunction "4_4") (pintype "passive"))
      (node (ref "R64") (pin "1") (pinfunction "1_1") (pintype "passive"))
    )
    (net (code "25") (name "/Opto_Y_IN") (class "Default")
      (node (ref "C72") (pin "1") (pinfunction "1_1") (pintype "passive"))
      (node (ref "D4") (pin "1") (pinfunction "K_1") (pintype "passive"))
      (node (ref "J6") (pin "3") (pinfunction "3_3") (pintype "passive"))
      (node (ref "J6") (pin "4") (pinfunction "4_4") (pintype "passive"))
      (node (ref "R97") (pin "1") (pinfunction "1_1") (pintype "passive"))
    )
    (net (code "26") (name "/Opto_Z_IN") (class "Default")
      (node (ref "C73") (pin "1") (pinfunction "1_1") (pintype "passive"))
      (node (ref "D7") (pin "1") (pinfunction "K_1") (pintype "passive"))
      (node (ref "J9") (pin "3") (pinfunction "3_3") (pintype "passive"))
      (node (ref "J9") (pin "4") (pinfunction "4_4") (pintype "passive"))
      (node (ref "R104") (pin "1") (pinfunction "1_1") (pintype "passive"))
    )
    (net (code "27") (name "/X_Motor_1A") (class "Default")
      (node (ref "J1") (pin "2") (pinfunction "2_2") (pintype "passive"))
      (node (ref "U1") (pin "24") (pinfunction "OUT1A_24") (pintype "passive"))
    )
    (net (code "28") (name "/X_Motor_1B") (class "Default")
      (node (ref "J1") (pin "1") (pinfunction "1_1") (pintype "passive"))
      (node (ref "U1") (pin "21") (pinfunction "OUT1B_21") (pintype "passive"))
    )
    (net (code "29") (name "/X_Motor_2A") (class "Default")
      (node (ref "J1") (pin "3") (pinfunction "3_3") (pintype "passive"))
      (node (ref "U1") (pin "26") (pinfunction "OUT2A_26") (pintype "passive"))
    )
    (net (code "30") (name "/X_Motor_2B") (class "Default")
      (node (ref "J1") (pin "4") (pinfunction "4_4") (pintype "passive"))
      (node (ref "U1") (pin "1") (pinfunction "OUT2B_1") (pintype "passive"))
    )
    (net (code "31") (name "/Y_Motor_1A") (class "Default")
      (node (ref "J2") (pin "2") (pinfunction "2_2") (pintype "passive"))
      (node (ref "U2") (pin "24") (pinfunction "OUT1A_24") (pintype "passive"))
    )
    (net (code "32") (name "/Y_Motor_1B") (class "Default")
      (node (ref "J2") (pin "1") (pinfunction "1_1") (pintype "passive"))
      (node (ref "U2") (pin "21") (pinfunction "OUT1B_21") (pintype "passive"))
    )
    (net (code "33") (name "/Y_Motor_2A") (class "Default")
      (node (ref "J2") (pin "3") (pinfunction "3_3") (pintype "passive"))
      (node (ref "U2") (pin "26") (pinfunction "OUT2A_26") (pintype "passive"))
    )
    (net (code "34") (name "/Y_Motor_2B") (class "Default")
      (node (ref "J2") (pin "4") (pinfunction "4_4") (pintype "passive"))
      (node (ref "U2") (pin "1") (pinfunction "OUT2B_1") (pintype "passive"))
    )
    (net (code "35") (name "/Z_Motor_1A") (class "Default")
      (node (ref "J4") (pin "2") (pinfunction "2_2") (pintype "passive"))
      (node (ref "U3") (pin "24") (pinfunction "OUT1A_24") (pintype "passive"))
    )
    (net (code "36") (name "/Z_Motor_1B") (class "Default")
      (node (ref "J4") (pin "1") (pinfunction "1_1") (pintype "passive"))
      (node (ref "U3") (pin "21") (pinfunction "OUT1B_21") (pintype "passive"))
    )
    (net (code "37") (name "/Z_Motor_2A") (class "Default")
      (node (ref "J4") (pin "3") (pinfunction "3_3") (pintype "passive"))
      (node (ref "U3") (pin "26") (pinfunction "OUT2A_26") (pintype "passive"))
    )
    (net (code "38") (name "/Z_Motor_2B") (class "Default")
      (node (ref "J4") (pin "4") (pinfunction "4_4") (pintype "passive"))
      (node (ref "U3") (pin "1") (pinfunction "OUT2B_1") (pintype "passive"))
    )
    (net (code "39") (name "/ctc1") (class "Default")
      (node (ref "R82") (pin "2") (pinfunction "2_2") (pintype "passive"))
      (node (ref "R88") (pin "1") (pinfunction "1_1") (pintype "passive"))
      (node (ref "R94") (pin "2") (pinfunction "2_2") (pintype "passive"))
    )
    (net (code "40") (name "/ctc2") (class "Default")
      (node (ref "R10") (pin "1") (pinfunction "1_1") (pintype "passive"))
      (node (ref "R105") (pin "2") (pinfunction "2_2") (pintype "passive"))
      (node (ref "R92") (pin "2") (pinfunction "2_2") (pintype "passive"))
    )
    (net (code "41") (name "/heat_bed") (class "Default")
      (node (ref "D16") (pin "2") (pinfunction "A_2") (pintype "passive"))
      (node (ref "J7") (pin "4") (pinfunction "4_4") (pintype "passive"))
      (node (ref "Q14") (pin "D") (pinfunction "D_D") (pintype "passive"))
    )
    (net (code "42") (name "/heat_ext") (class "Default")
      (node (ref "D15") (pin "2") (pinfunction "A_2") (pintype "passive"))
      (node (ref "J8") (pin "4") (pinfunction "4_4") (pintype "passive"))
      (node (ref "Q15") (pin "D") (pinfunction "D_D") (pintype "passive"))
    )
    (net (code "43") (name "GND") (class "Default")
      (node (ref "C15") (pin "1") (pinfunction "1_1") (pintype "passive"))
      (node (ref "C16") (pin "1") (pinfunction "1_1") (pintype "passive"))
      (node (ref "C17") (pin "1") (pinfunction "1_1") (pintype "passive"))
      (node (ref "C18") (pin "2") (pinfunction "2_2") (pintype "passive"))
      (node (ref "C21") (pin "1") (pinfunction "1_1") (pintype "passive"))
      (node (ref "C22") (pin "1") (pinfunction "1_1") (pintype "passive"))
      (node (ref "C23") (pin "1") (pinfunction "1_1") (pintype "passive"))
      (node (ref "C24") (pin "1") (pinfunction "1_1") (pintype "passive"))
      (node (ref "C3") (pin "1") (pinfunction "1_1") (pintype "passive"))
      (node (ref "C33") (pin "1") (pinfunction "1_1") (pintype "passive"))
      (node (ref "C34") (pin "1") (pinfunction "1_1") (pintype "passive"))
      (node (ref "C35") (pin "1") (pinfunction "1_1") (pintype "passive"))
      (node (ref "C36") (pin "1") (pinfunction "1_1") (pintype "passive"))
      (node (ref "C4") (pin "1") (pinfunction "1_1") (pintype "passive"))
      (node (ref "C5") (pin "1") (pinfunction "1_1") (pintype "passive"))
      (node (ref "C6") (pin "1") (pinfunction "1_1") (pintype "passive"))
      (node (ref "P1") (pin "3") (pinfunction "TOP_3") (pintype "passive"))
      (node (ref "P2") (pin "3") (pinfunction "TOP_3") (pintype "passive"))
      (node (ref "P3") (pin "3") (pinfunction "TOP_3") (pintype "passive"))
      (node (ref "P4") (pin "3") (pinfunction "TOP_3") (pintype "passive"))
      (node (ref "Q1") (pin "2") (pinfunction "S_2") (pintype "passive"))
      (node (ref "Q2") (pin "2") (pinfunction "S_2") (pintype "passive"))
      (node (ref "Q3") (pin "2") (pinfunction "S_2") (pintype "passive"))
      (node (ref "Q4") (pin "2") (pinfunction "S_2") (pintype "passive"))
      (node (ref "Q5") (pin "2") (pinfunction "S_2") (pintype "passive"))
      (node (ref "Q6") (pin "2") (pinfunction "S_2") (pintype "passive"))
      (node (ref "R105") (pin "1") (pinfunction "1_1") (pintype "passive"))
      (node (ref "R26") (pin "1") (pinfunction "1_1") (pintype "passive"))
      (node (ref "R27") (pin "1") (pinfunction "1_1") (pintype "passive"))
      (node (ref "R28") (pin "1") (pinfunction "1_1") (pintype "passive"))
      (node (ref "R29") (pin "1") (pinfunction "1_1") (pintype "passive"))
      (node (ref "R55") (pin "1") (pinfunction "1_1") (pintype "passive"))
      (node (ref "R56") (pin "1") (pinfunction "1_1") (pintype "passive"))
      (node (ref "R57") (pin "1") (pinfunction "1_1") (pintype "passive"))
      (node (ref "R58") (pin "1") (pinfunction "1_1") (pintype "passive"))
      (node (ref "R94") (pin "1") (pinfunction "1_1") (pintype "passive"))
    )
    (net (code "44") (name "GND_A") (class "Default")
      (node (ref "C37") (pin "1") (pinfunction "1_1") (pintype "passive"))
      (node (ref "C38") (pin "1") (pinfunction "1_1") (pintype "passive"))
      (node (ref "C39") (pin "1") (pinfunction "1_1") (pintype "passive"))
      (node (ref "C40") (pin "1") (pinfunction "1_1") (pintype "passive"))
      (node (ref "L3") (pin "1") (pinfunction "1_1") (pintype "passive"))
      (node (ref "L4") (pin "1") (pinfunction "1_1") (pintype "passive"))
    )
    (net (code "45") (name "Net-(D1-A)") (class "Default")
      (node (ref "D1") (pin "2") (pinfunction "A_2") (pintype "passive"))
      (node (ref "R13") (pin "1") (pinfunction "1_1") (pintype "passive"))
    )
    (net (code "46") (name "Net-(D2-K)") (class "Default")
      (node (ref "D2") (pin "1") (pinfunction "K_1") (pintype "passive"))
      (node (ref "R16") (pin "2") (pinfunction "2_2") (pintype "passive"))
    )
    (net (code "47") (name "Net-(D3-K)") (class "Default")
      (node (ref "D3") (pin "1") (pinfunction "K_1") (pintype "passive"))
      (node (ref "R17") (pin "2") (pinfunction "2_2") (pintype "passive"))
    )
    (net (code "48") (name "Net-(D4-A)") (class "Default")
      (node (ref "D4") (pin "2") (pinfunction "A_2") (pintype "passive"))
      (node (ref "R42") (pin "1") (pinfunction "1_1") (pintype "passive"))
    )
    (net (code "49") (name "Net-(D5-K)") (class "Default")
      (node (ref "D5") (pin "1") (pinfunction "K_1") (pintype "passive"))
      (node (ref "R46") (pin "2") (pinfunction "2_2") (pintype "passive"))
    )
    (net (code "50") (name "Net-(D6-K)") (class "Default")
      (node (ref "D6") (pin "1") (pinfunction "K_1") (pintype "passive"))
      (node (ref "R61") (pin "2") (pinfunction "2_2") (pintype "passive"))
    )
    (net (code "51") (name "Net-(D7-A)") (class "Default")
      (node (ref "D7") (pin "2") (pinfunction "A_2") (pintype "passive"))
      (node (ref "R45") (pin "1") (pinfunction "1_1") (pintype "passive"))
    )
    (net (code "52") (name "Net-(D8-K)") (class "Default")
      (node (ref "D8") (pin "1") (pinfunction "K_1") (pintype "passive"))
      (node (ref "R80") (pin "2") (pinfunction "2_2") (pintype "passive"))
    )
    (net (code "53") (name "Net-(D9-K)") (class "Default")
      (node (ref "D9") (pin "1") (pinfunction "K_1") (pintype "passive"))
      (node (ref "R81") (pin "2") (pinfunction "2_2") (pintype "passive"))
    )
    (net (code "54") (name "Net-(P1-BOT)") (class "Default")
      (node (ref "C17") (pin "2") (pinfunction "2_2") (pintype "passive"))
      (node (ref "P1") (pin "1") (pinfunction "BOT_1") (pintype "passive"))
      (node (ref "R18") (pin "1") (pinfunction "1_1") (pintype "passive"))
    )
    (net (code "55") (name "Net-(P1-TAP)") (class "Default")
      (node (ref "P1") (pin "2") (pinfunction "TAP_2") (pintype "passive"))
      (node (ref "U1") (pin "17") (pinfunction "REF_17") (pintype "passive"))
    )
    (net (code "56") (name "Net-(P2-BOT)") (class "Default")
      (node (ref "C18") (pin "1") (pinfunction "1_1") (pintype "passive"))
      (node (ref "P2") (pin "1") (pinfunction "BOT_1") (pintype "passive"))
      (node (ref "R19") (pin "1") (pinfunction "1_1") (pintype "passive"))
    )
    (net (code "57") (name "Net-(P2-TAP)") (class "Default")
      (node (ref "P2") (pin "2") (pinfunction "TAP_2") (pintype "passive"))
      (node (ref "U2") (pin "17") (pinfunction "REF_17") (pintype "passive"))
    )
    (net (code "58") (name "Net-(P3-BOT)") (class "Default")
      (node (ref "C35") (pin "2") (pinfunction "2_2") (pintype "passive"))
      (node (ref "P3") (pin "1") (pinfunction "BOT_1") (pintype "passive"))
      (node (ref "R47") (pin "1") (pinfunction "1_1") (pintype "passive"))
    )
    (net (code "59") (name "Net-(P3-TAP)") (class "Default")
      (node (ref "P3") (pin "2") (pinfunction "TAP_2") (pintype "passive"))
      (node (ref "U3") (pin "17") (pinfunction "REF_17") (pintype "passive"))
    )
    (net (code "60") (name "Net-(P4-BOT)") (class "Default")
      (node (ref "C36") (pin "2") (pinfunction "2_2") (pintype "passive"))
      (node (ref "P4") (pin "1") (pinfunction "BOT_1") (pintype "passive"))
      (node (ref "R48") (pin "1") (pinfunction "1_1") (pintype "passive"))
    )
    (net (code "61") (name "Net-(P4-TAP)") (class "Default")
      (node (ref "P4") (pin "2") (pinfunction "TAP_2") (pintype "passive"))
      (node (ref "U4") (pin "17") (pinfunction "REF_17") (pintype "passive"))
    )
    (net (code "62") (name "Net-(Q1-D)") (class "Default")
      (node (ref "Q1") (pin "3") (pinfunction "D_3") (pintype "passive"))
      (node (ref "R16") (pin "1") (pinfunction "1_1") (pintype "passive"))
    )
    (net (code "63") (name "Net-(Q1-G)") (class "Default")
      (node (ref "Q1") (pin "1") (pinfunction "G_1") (pintype "passive"))
      (node (ref "R24") (pin "1") (pinfunction "1_1") (pintype "passive"))
    )
    (net (code "64") (name "Net-(Q2-D)") (class "Default")
      (node (ref "Q2") (pin "3") (pinfunction "D_3") (pintype "passive"))
      (node (ref "R17") (pin "1") (pinfunction "1_1") (pintype "passive"))
    )
    (net (code "65") (name "Net-(Q2-G)") (class "Default")
      (node (ref "Q2") (pin "1") (pinfunction "G_1") (pintype "passive"))
      (node (ref "R25") (pin "1") (pinfunction "1_1") (pintype "passive"))
    )
    (net (code "66") (name "Net-(Q3-D)") (class "Default")
      (node (ref "Q3") (pin "3") (pinfunction "D_3") (pintype "passive"))
      (node (ref "R46") (pin "1") (pinfunction "1_1") (pintype "passive"))
    )
    (net (code "67") (name "Net-(Q3-G)") (class "Default")
      (node (ref "Q3") (pin "1") (pinfunction "G_1") (pintype "passive"))
      (node (ref "R53") (pin "1") (pinfunction "1_1") (pintype "passive"))
    )
    (net (code "68") (name "Net-(Q4-D)") (class "Default")
      (node (ref "Q4") (pin "3") (pinfunction "D_3") (pintype "passive"))
      (node (ref "R61") (pin "1") (pinfunction "1_1") (pintype "passive"))
    )
    (net (code "69") (name "Net-(Q4-G)") (class "Default")
      (node (ref "Q4") (pin "1") (pinfunction "G_1") (pintype "passive"))
      (node (ref "R54") (pin "1") (pinfunction "1_1") (pintype "passive"))
    )
    (net (code "70") (name "Net-(Q5-D)") (class "Default")
      (node (ref "Q5") (pin "3") (pinfunction "D_3") (pintype "passive"))
      (node (ref "R81") (pin "1") (pinfunction "1_1") (pintype "passive"))
    )
    (net (code "71") (name "Net-(Q5-G)") (class "Default")
      (node (ref "Q5") (pin "1") (pinfunction "G_1") (pintype "passive"))
      (node (ref "R92") (pin "1") (pinfunction "1_1") (pintype "passive"))
    )
    (net (code "72") (name "Net-(Q6-D)") (class "Default")
      (node (ref "Q6") (pin "3") (pinfunction "D_3") (pintype "passive"))
      (node (ref "R80") (pin "1") (pinfunction "1_1") (pintype "passive"))
    )
    (net (code "73") (name "Net-(Q6-G)") (class "Default")
      (node (ref "Q6") (pin "1") (pinfunction "G_1") (pintype "passive"))
      (node (ref "R82") (pin "1") (pinfunction "1_1") (pintype "passive"))
    )
    (net (code "74") (name "Net-(Q14-PadG)") (class "Default")
      (node (ref "Q14") (pin "G") (pinfunction "G_G") (pintype "passive"))
      (node (ref "R10") (pin "2") (pinfunction "2_2") (pintype "passive"))
      (node (ref "R14") (pin "2") (pinfunction "2_2") (pintype "passive"))
    )
    (net (code "75") (name "Net-(Q15-PadG)") (class "Default")
      (node (ref "Q15") (pin "G") (pinfunction "G_G") (pintype "passive"))
      (node (ref "R5") (pin "2") (pinfunction "2_2") (pintype "passive"))
      (node (ref "R88") (pin "2") (pinfunction "2_2") (pintype "passive"))
    )
    (net (code "76") (name "Net-(U1-CP1)") (class "Default")
      (node (ref "C1") (pin "2") (pinfunction "2_2") (pintype "passive"))
      (node (ref "U1") (pin "4") (pinfunction "CP1_4") (pintype "passive"))
    )
    (net (code "77") (name "Net-(U1-CP2)") (class "Default")
      (node (ref "C1") (pin "1") (pinfunction "1_1") (pintype "passive"))
      (node (ref "U1") (pin "5") (pinfunction "CP2_5") (pintype "passive"))
    )
    (net (code "78") (name "Net-(U1-MS1)") (class "Default")
      (node (ref "R1") (pin "1") (pinfunction "1_1") (pintype "passive"))
      (node (ref "R28") (pin "2") (pinfunction "2_2") (pintype "passive"))
      (node (ref "U1") (pin "9") (pinfunction "MS1_9") (pintype "input"))
    )
    (net (code "79") (name "Net-(U1-MS2)") (class "Default")
      (node (ref "R2") (pin "1") (pinfunction "1_1") (pintype "passive"))
      (node (ref "U1") (pin "10") (pinfunction "MS2_10") (pintype "input"))
    )
    (net (code "80") (name "Net-(U1-MS3)") (class "Default")
      (node (ref "R3") (pin "1") (pinfunction "1_1") (pintype "passive"))
      (node (ref "U1") (pin "11") (pinfunction "MS3_11") (pintype "input"))
    )
    (net (code "81") (name "Net-(U1-ROSC)") (class "Default")
      (node (ref "R26") (pin "2") (pinfunction "2_2") (pintype "passive"))
      (node (ref "U1") (pin "13") (pinfunction "ROSC_13") (pintype "passive"))
    )
    (net (code "82") (name "Net-(U1-SENSE1)") (class "Default")
      (node (ref "R21") (pin "2") (pinfunction "2_2") (pintype "passive"))
      (node (ref "U1") (pin "23") (pinfunction "SENSE1_23") (pintype "passive"))
    )
    (net (code "83") (name "Net-(U1-SENSE2)") (class "Default")
      (node (ref "R20") (pin "2") (pinfunction "2_2") (pintype "passive"))
      (node (ref "U1") (pin "27") (pinfunction "SENSE2_27") (pintype "passive"))
    )
    (net (code "84") (name "Net-(U1-SLEEP)") (class "Default")
      (node (ref "R6") (pin "1") (pinfunction "1_1") (pintype "passive"))
      (node (ref "U1") (pin "14") (pinfunction "SLEEP_14") (pintype "passive"))
    )
    (net (code "85") (name "Net-(U1-VCP)") (class "Default")
      (node (ref "C13") (pin "1") (pinfunction "1_1") (pintype "passive"))
      (node (ref "U1") (pin "6") (pinfunction "VCP_6") (pintype "passive"))
    )
    (net (code "86") (name "Net-(U1-VREG)") (class "Default")
      (node (ref "C15") (pin "2") (pinfunction "2_2") (pintype "passive"))
      (node (ref "U1") (pin "8") (pinfunction "VREG_8") (pintype "passive"))
    )
    (net (code "87") (name "Net-(U2-CP1)") (class "Default")
      (node (ref "C2") (pin "1") (pinfunction "1_1") (pintype "passive"))
      (node (ref "U2") (pin "4") (pinfunction "CP1_4") (pintype "passive"))
    )
    (net (code "88") (name "Net-(U2-CP2)") (class "Default")
      (node (ref "C2") (pin "2") (pinfunction "2_2") (pintype "passive"))
      (node (ref "U2") (pin "5") (pinfunction "CP2_5") (pintype "passive"))
    )
    (net (code "89") (name "Net-(U2-MS1)") (class "Default")
      (node (ref "R29") (pin "2") (pinfunction "2_2") (pintype "passive"))
      (node (ref "R7") (pin "1") (pinfunction "1_1") (pintype "passive"))
      (node (ref "U2") (pin "9") (pinfunction "MS1_9") (pintype "input"))
    )
    (net (code "90") (name "Net-(U2-MS2)") (class "Default")
      (node (ref "R8") (pin "1") (pinfunction "1_1") (pintype "passive"))
      (node (ref "U2") (pin "10") (pinfunction "MS2_10") (pintype "input"))
    )
    (net (code "91") (name "Net-(U2-MS3)") (class "Default")
      (node (ref "R9") (pin "1") (pinfunction "1_1") (pintype "passive"))
      (node (ref "U2") (pin "11") (pinfunction "MS3_11") (pintype "input"))
    )
    (net (code "92") (name "Net-(U2-ROSC)") (class "Default")
      (node (ref "R27") (pin "2") (pinfunction "2_2") (pintype "passive"))
      (node (ref "U2") (pin "13") (pinfunction "ROSC_13") (pintype "passive"))
    )
    (net (code "93") (name "Net-(U2-SENSE1)") (class "Default")
      (node (ref "R23") (pin "2") (pinfunction "2_2") (pintype "passive"))
      (node (ref "U2") (pin "23") (pinfunction "SENSE1_23") (pintype "passive"))
    )
    (net (code "94") (name "Net-(U2-SENSE2)") (class "Default")
      (node (ref "R22") (pin "2") (pinfunction "2_2") (pintype "passive"))
      (node (ref "U2") (pin "27") (pinfunction "SENSE2_27") (pintype "passive"))
    )
    (net (code "95") (name "Net-(U2-SLEEP)") (class "Default")
      (node (ref "R12") (pin "1") (pinfunction "1_1") (pintype "passive"))
      (node (ref "U2") (pin "14") (pinfunction "SLEEP_14") (pintype "passive"))
    )
    (net (code "96") (name "Net-(U2-VCP)") (class "Default")
      (node (ref "C14") (pin "1") (pinfunction "1_1") (pintype "passive"))
      (node (ref "U2") (pin "6") (pinfunction "VCP_6") (pintype "passive"))
    )
    (net (code "97") (name "Net-(U2-VREG)") (class "Default")
      (node (ref "C16") (pin "2") (pinfunction "2_2") (pintype "passive"))
      (node (ref "U2") (pin "8") (pinfunction "VREG_8") (pintype "passive"))
    )
    (net (code "98") (name "Net-(U3-CP1)") (class "Default")
      (node (ref "C19") (pin "2") (pinfunction "2_2") (pintype "passive"))
      (node (ref "U3") (pin "4") (pinfunction "CP1_4") (pintype "passive"))
    )
    (net (code "99") (name "Net-(U3-CP2)") (class "Default")
      (node (ref "C19") (pin "1") (pinfunction "1_1") (pintype "passive"))
      (node (ref "U3") (pin "5") (pinfunction "CP2_5") (pintype "passive"))
    )
    (net (code "100") (name "Net-(U3-MS1)") (class "Default")
      (node (ref "R30") (pin "1") (pinfunction "1_1") (pintype "passive"))
      (node (ref "R56") (pin "2") (pinfunction "2_2") (pintype "passive"))
      (node (ref "U3") (pin "9") (pinfunction "MS1_9") (pintype "input"))
    )
    (net (code "101") (name "Net-(U3-MS2)") (class "Default")
      (node (ref "R31") (pin "1") (pinfunction "1_1") (pintype "passive"))
      (node (ref "U3") (pin "10") (pinfunction "MS2_10") (pintype "input"))
    )
    (net (code "102") (name "Net-(U3-MS3)") (class "Default")
      (node (ref "R32") (pin "1") (pinfunction "1_1") (pintype "passive"))
      (node (ref "U3") (pin "11") (pinfunction "MS3_11") (pintype "input"))
    )
    (net (code "103") (name "Net-(U3-ROSC)") (class "Default")
      (node (ref "R55") (pin "2") (pinfunction "2_2") (pintype "passive"))
      (node (ref "U3") (pin "13") (pinfunction "ROSC_13") (pintype "passive"))
    )
    (net (code "104") (name "Net-(U3-SENSE1)") (class "Default")
      (node (ref "R50") (pin "2") (pinfunction "2_2") (pintype "passive"))
      (node (ref "U3") (pin "23") (pinfunction "SENSE1_23") (pintype "passive"))
    )
    (net (code "105") (name "Net-(U3-SENSE2)") (class "Default")
      (node (ref "R49") (pin "2") (pinfunction "2_2") (pintype "passive"))
      (node (ref "U3") (pin "27") (pinfunction "SENSE2_27") (pintype "passive"))
    )
    (net (code "106") (name "Net-(U3-SLEEP)") (class "Default")
      (node (ref "R35") (pin "1") (pinfunction "1_1") (pintype "passive"))
      (node (ref "U3") (pin "14") (pinfunction "SLEEP_14") (pintype "passive"))
    )
    (net (code "107") (name "Net-(U3-VCP)") (class "Default")
      (node (ref "C30") (pin "1") (pinfunction "1_1") (pintype "passive"))
      (node (ref "U3") (pin "6") (pinfunction "VCP_6") (pintype "passive"))
    )
    (net (code "108") (name "Net-(U3-VREG)") (class "Default")
      (node (ref "C33") (pin "2") (pinfunction "2_2") (pintype "passive"))
      (node (ref "U3") (pin "8") (pinfunction "VREG_8") (pintype "passive"))
    )
    (net (code "109") (name "Net-(U4-CP1)") (class "Default")
      (node (ref "C20") (pin "1") (pinfunction "1_1") (pintype "passive"))
      (node (ref "U4") (pin "4") (pinfunction "CP1_4") (pintype "passive"))
    )
    (net (code "110") (name "Net-(U4-CP2)") (class "Default")
      (node (ref "C20") (pin "2") (pinfunction "2_2") (pintype "passive"))
      (node (ref "U4") (pin "5") (pinfunction "CP2_5") (pintype "passive"))
    )
    (net (code "111") (name "Net-(U4-MS1)") (class "Default")
      (node (ref "R36") (pin "1") (pinfunction "1_1") (pintype "passive"))
      (node (ref "R58") (pin "2") (pinfunction "2_2") (pintype "passive"))
      (node (ref "U4") (pin "9") (pinfunction "MS1_9") (pintype "input"))
    )
    (net (code "112") (name "Net-(U4-MS2)") (class "Default")
      (node (ref "R37") (pin "1") (pinfunction "1_1") (pintype "passive"))
      (node (ref "U4") (pin "10") (pinfunction "MS2_10") (pintype "input"))
    )
    (net (code "113") (name "Net-(U4-MS3)") (class "Default")
      (node (ref "R38") (pin "1") (pinfunction "1_1") (pintype "passive"))
      (node (ref "U4") (pin "11") (pinfunction "MS3_11") (pintype "input"))
    )
    (net (code "114") (name "Net-(U4-ROSC)") (class "Default")
      (node (ref "R57") (pin "2") (pinfunction "2_2") (pintype "passive"))
      (node (ref "U4") (pin "13") (pinfunction "ROSC_13") (pintype "passive"))
    )
    (net (code "115") (name "Net-(U4-SENSE1)") (class "Default")
      (node (ref "R52") (pin "2") (pinfunction "2_2") (pintype "passive"))
      (node (ref "U4") (pin "23") (pinfunction "SENSE1_23") (pintype "passive"))
    )
    (net (code "116") (name "Net-(U4-SENSE2)") (class "Default")
      (node (ref "R51") (pin "2") (pinfunction "2_2") (pintype "passive"))
      (node (ref "U4") (pin "27") (pinfunction "SENSE2_27") (pintype "passive"))
    )
    (net (code "117") (name "Net-(U4-SLEEP)") (class "Default")
      (node (ref "R41") (pin "1") (pinfunction "1_1") (pintype "passive"))
      (node (ref "U4") (pin "14") (pinfunction "SLEEP_14") (pintype "passive"))
    )
    (net (code "118") (name "Net-(U4-VCP)") (class "Default")
      (node (ref "C32") (pin "1") (pinfunction "1_1") (pintype "passive"))
      (node (ref "U4") (pin "6") (pinfunction "VCP_6") (pintype "passive"))
    )
    (net (code "119") (name "Net-(U4-VREG)") (class "Default")
      (node (ref "C34") (pin "2") (pinfunction "2_2") (pintype "passive"))
      (node (ref "U4") (pin "8") (pinfunction "VREG_8") (pintype "passive"))
    )
    (net (code "120") (name "Star_GND") (class "Default")
      (node (ref "C10") (pin "1") (pinfunction "1_1") (pintype "passive"))
      (node (ref "C11") (pin "2") (pinfunction "2_2") (pintype "passive"))
      (node (ref "C12") (pin "2") (pinfunction "2_2") (pintype "passive"))
      (node (ref "C25") (pin "1") (pinfunction "1_1") (pintype "passive"))
      (node (ref "C26") (pin "1") (pinfunction "1_1") (pintype "passive"))
      (node (ref "C27") (pin "2") (pinfunction "2_2") (pintype "passive"))
      (node (ref "C28") (pin "1") (pinfunction "1_1") (pintype "passive"))
      (node (ref "C29") (pin "1") (pinfunction "1_1") (pintype "passive"))
      (node (ref "C31") (pin "2") (pinfunction "2_2") (pintype "passive"))
      (node (ref "C62") (pin "1") (pinfunction "1_1") (pintype "passive"))
      (node (ref "C7") (pin "2") (pinfunction "2_2") (pintype "passive"))
      (node (ref "C71") (pin "2") (pinfunction "2_2") (pintype "passive"))
      (node (ref "C72") (pin "2") (pinfunction "2_2") (pintype "passive"))
      (node (ref "C73") (pin "2") (pinfunction "2_2") (pintype "passive"))
      (node (ref "C8") (pin "1") (pinfunction "1_1") (pintype "passive"))
      (node (ref "C9") (pin "1") (pinfunction "1_1") (pintype "passive"))
      (node (ref "J21") (pin "2") (pinfunction "2_2") (pintype "passive"))
      (node (ref "J3") (pin "5") (pinfunction "5_5") (pintype "passive"))
      (node (ref "J3") (pin "6") (pinfunction "6_6") (pintype "passive"))
      (node (ref "J6") (pin "5") (pinfunction "5_5") (pintype "passive"))
      (node (ref "J6") (pin "6") (pinfunction "6_6") (pintype "passive"))
      (node (ref "J9") (pin "5") (pinfunction "5_5") (pintype "passive"))
      (node (ref "J9") (pin "6") (pinfunction "6_6") (pintype "passive"))
      (node (ref "Q14") (pin "S") (pinfunction "S_S") (pintype "passive"))
      (node (ref "Q15") (pin "S") (pinfunction "S_S") (pintype "passive"))
      (node (ref "R14") (pin "1") (pinfunction "1_1") (pintype "passive"))
      (node (ref "R20") (pin "1") (pinfunction "1_1") (pintype "passive"))
      (node (ref "R21") (pin "1") (pinfunction "1_1") (pintype "passive"))
      (node (ref "R22") (pin "1") (pinfunction "1_1") (pintype "passive"))
      (node (ref "R23") (pin "1") (pinfunction "1_1") (pintype "passive"))
      (node (ref "R49") (pin "1") (pinfunction "1_1") (pintype "passive"))
      (node (ref "R5") (pin "1") (pinfunction "1_1") (pintype "passive"))
      (node (ref "R50") (pin "1") (pinfunction "1_1") (pintype "passive"))
      (node (ref "R51") (pin "1") (pinfunction "1_1") (pintype "passive"))
      (node (ref "R52") (pin "1") (pinfunction "1_1") (pintype "passive"))
      (node (ref "U1") (pin "18") (pinfunction "GND_18") (pintype "passive"))
      (node (ref "U1") (pin "29") (pinfunction "PAD_29") (pintype "passive"))
      (node (ref "U1") (pin "3") (pinfunction "GND_3") (pintype "passive"))
      (node (ref "U2") (pin "18") (pinfunction "GND_18") (pintype "passive"))
      (node (ref "U2") (pin "29") (pinfunction "PAD_29") (pintype "passive"))
      (node (ref "U2") (pin "3") (pinfunction "GND_3") (pintype "passive"))
      (node (ref "U3") (pin "18") (pinfunction "GND_18") (pintype "passive"))
      (node (ref "U3") (pin "29") (pinfunction "PAD_29") (pintype "passive"))
      (node (ref "U3") (pin "3") (pinfunction "GND_3") (pintype "passive"))
      (node (ref "U4") (pin "18") (pinfunction "GND_18") (pintype "passive"))
      (node (ref "U4") (pin "29") (pinfunction "PAD_29") (pintype "passive"))
      (node (ref "U4") (pin "3") (pinfunction "GND_3") (pintype "passive"))
    )
    (net (code "121") (name "V3.3") (class "Default")
      (node (ref "C21") (pin "2") (pinfunction "2_2") (pintype "passive"))
      (node (ref "C22") (pin "2") (pinfunction "2_2") (pintype "passive"))
      (node (ref "C23") (pin "2") (pinfunction "2_2") (pintype "passive"))
      (node (ref "C24") (pin "2") (pinfunction "2_2") (pintype "passive"))
      (node (ref "C3") (pin "2") (pinfunction "2_2") (pintype "passive"))
      (node (ref "C4") (pin "2") (pinfunction "2_2") (pintype "passive"))
      (node (ref "C5") (pin "2") (pinfunction "2_2") (pintype "passive"))
      (node (ref "C6") (pin "2") (pinfunction "2_2") (pintype "passive"))
      (node (ref "D2") (pin "2") (pinfunction "A_2") (pintype "passive"))
      (node (ref "D3") (pin "2") (pinfunction "A_2") (pintype "passive"))
      (node (ref "D5") (pin "2") (pinfunction "A_2") (pintype "passive"))
      (node (ref "D6") (pin "2") (pinfunction "A_2") (pintype "passive"))
      (node (ref "D8") (pin "2") (pinfunction "A_2") (pintype "passive"))
      (node (ref "D9") (pin "2") (pinfunction "A_2") (pintype "passive"))
      (node (ref "R1") (pin "2") (pinfunction "2_2") (pintype "passive"))
      (node (ref "R104") (pin "2") (pinfunction "2_2") (pintype "passive"))
      (node (ref "R12") (pin "2") (pinfunction "2_2") (pintype "passive"))
      (node (ref "R13") (pin "2") (pinfunction "2_2") (pintype "passive"))
      (node (ref "R18") (pin "2") (pinfunction "2_2") (pintype "passive"))
      (node (ref "R19") (pin "2") (pinfunction "2_2") (pintype "passive"))
      (node (ref "R2") (pin "2") (pinfunction "2_2") (pintype "passive"))
      (node (ref "R3") (pin "2") (pinfunction "2_2") (pintype "passive"))
      (node (ref "R30") (pin "2") (pinfunction "2_2") (pintype "passive"))
      (node (ref "R31") (pin "2") (pinfunction "2_2") (pintype "passive"))
      (node (ref "R32") (pin "2") (pinfunction "2_2") (pintype "passive"))
      (node (ref "R35") (pin "2") (pinfunction "2_2") (pintype "passive"))
      (node (ref "R36") (pin "2") (pinfunction "2_2") (pintype "passive"))
      (node (ref "R37") (pin "2") (pinfunction "2_2") (pintype "passive"))
      (node (ref "R38") (pin "2") (pinfunction "2_2") (pintype "passive"))
      (node (ref "R41") (pin "2") (pinfunction "2_2") (pintype "passive"))
      (node (ref "R42") (pin "2") (pinfunction "2_2") (pintype "passive"))
      (node (ref "R45") (pin "2") (pinfunction "2_2") (pintype "passive"))
      (node (ref "R47") (pin "2") (pinfunction "2_2") (pintype "passive"))
      (node (ref "R48") (pin "2") (pinfunction "2_2") (pintype "passive"))
      (node (ref "R6") (pin "2") (pinfunction "2_2") (pintype "passive"))
      (node (ref "R64") (pin "2") (pinfunction "2_2") (pintype "passive"))
      (node (ref "R7") (pin "2") (pinfunction "2_2") (pintype "passive"))
      (node (ref "R8") (pin "2") (pinfunction "2_2") (pintype "passive"))
      (node (ref "R9") (pin "2") (pinfunction "2_2") (pintype "passive"))
      (node (ref "R97") (pin "2") (pinfunction "2_2") (pintype "passive"))
      (node (ref "U1") (pin "15") (pinfunction "VDD_15") (pintype "passive"))
      (node (ref "U2") (pin "15") (pinfunction "VDD_15") (pintype "passive"))
      (node (ref "U3") (pin "15") (pinfunction "VDD_15") (pintype "passive"))
      (node (ref "U4") (pin "15") (pinfunction "VDD_15") (pintype "passive"))
    )
    (net (code "122") (name "V5") (class "Default")
      (node (ref "J3") (pin "1") (pinfunction "1_1") (pintype "passive"))
      (node (ref "J3") (pin "2") (pinfunction "2_2") (pintype "passive"))
      (node (ref "J6") (pin "1") (pinfunction "1_1") (pintype "passive"))
      (node (ref "J6") (pin "2") (pinfunction "2_2") (pintype "passive"))
      (node (ref "J9") (pin "1") (pinfunction "1_1") (pintype "passive"))
      (node (ref "J9") (pin "2") (pinfunction "2_2") (pintype "passive"))
    )
    (net (code "123") (name "VA3.3") (class "Default")
      (node (ref "R59") (pin "2") (pinfunction "2_2") (pintype "passive"))
      (node (ref "R60") (pin "2") (pinfunction "2_2") (pintype "passive"))
    )
    (net (code "124") (name "VMM") (class "Default")
      (node (ref "C10") (pin "2") (pinfunction "2_2") (pintype "passive"))
      (node (ref "C11") (pin "1") (pinfunction "1_1") (pintype "passive"))
      (node (ref "C12") (pin "1") (pinfunction "1_1") (pintype "passive"))
      (node (ref "C13") (pin "2") (pinfunction "2_2") (pintype "passive"))
      (node (ref "C14") (pin "2") (pinfunction "2_2") (pintype "passive"))
      (node (ref "C25") (pin "2") (pinfunction "2_2") (pintype "passive"))
      (node (ref "C26") (pin "2") (pinfunction "2_2") (pintype "passive"))
      (node (ref "C27") (pin "1") (pinfunction "1_1") (pintype "passive"))
      (node (ref "C28") (pin "2") (pinfunction "2_2") (pintype "passive"))
      (node (ref "C29") (pin "2") (pinfunction "2_2") (pintype "passive"))
      (node (ref "C30") (pin "2") (pinfunction "2_2") (pintype "passive"))
      (node (ref "C31") (pin "1") (pinfunction "1_1") (pintype "passive"))
      (node (ref "C32") (pin "2") (pinfunction "2_2") (pintype "passive"))
      (node (ref "C62") (pin "2") (pinfunction "2_2") (pintype "passive"))
      (node (ref "C7") (pin "1") (pinfunction "1_1") (pintype "passive"))
      (node (ref "C8") (pin "2") (pinfunction "2_2") (pintype "passive"))
      (node (ref "C9") (pin "2") (pinfunction "2_2") (pintype "passive"))
      (node (ref "D15") (pin "1") (pinfunction "K_1") (pintype "passive"))
      (node (ref "D16") (pin "1") (pinfunction "K_1") (pintype "passive"))
      (node (ref "J21") (pin "1") (pinfunction "1_1") (pintype "passive"))
      (node (ref "J7") (pin "3") (pinfunction "3_3") (pintype "passive"))
      (node (ref "J8") (pin "3") (pinfunction "3_3") (pintype "passive"))
      (node (ref "U1") (pin "22") (pinfunction "VBB1_22") (pintype "passive"))
      (node (ref "U1") (pin "28") (pinfunction "VBB2_28") (pintype "passive"))
      (node (ref "U2") (pin "22") (pinfunction "VBB1_22") (pintype "passive"))
      (node (ref "U2") (pin "28") (pinfunction "VBB2_28") (pintype "passive"))
      (node (ref "U3") (pin "22") (pinfunction "VBB1_22") (pintype "passive"))
      (node (ref "U3") (pin "28") (pinfunction "VBB2_28") (pintype "passive"))
      (node (ref "U4") (pin "22") (pinfunction "VBB1_22") (pintype "passive"))
      (node (ref "U4") (pin "28") (pinfunction "VBB2_28") (pintype "passive"))
    )
    (net (code "125") (name "unconnected-(U1-NC-Pad7)") (class "Default")
      (node (ref "U1") (pin "7") (pinfunction "NC_7") (pintype "passive+no_connect"))
    )
    (net (code "126") (name "unconnected-(U1-NC-Pad20)") (class "Default")
      (node (ref "U1") (pin "20") (pinfunction "NC_20") (pintype "passive+no_connect"))
    )
    (net (code "127") (name "unconnected-(U1-NC-Pad25)") (class "Default")
      (node (ref "U1") (pin "25") (pinfunction "NC_25") (pintype "passive+no_connect"))
    )
    (net (code "128") (name "unconnected-(U2-NC-Pad7)") (class "Default")
      (node (ref "U2") (pin "7") (pinfunction "NC_7") (pintype "passive+no_connect"))
    )
    (net (code "129") (name "unconnected-(U2-NC-Pad20)") (class "Default")
      (node (ref "U2") (pin "20") (pinfunction "NC_20") (pintype "passive+no_connect"))
    )
    (net (code "130") (name "unconnected-(U2-NC-Pad25)") (class "Default")
      (node (ref "U2") (pin "25") (pinfunction "NC_25") (pintype "passive+no_connect"))
    )
    (net (code "131") (name "unconnected-(U3-NC-Pad7)") (class "Default")
      (node (ref "U3") (pin "7") (pinfunction "NC_7") (pintype "passive+no_connect"))
    )
    (net (code "132") (name "unconnected-(U3-NC-Pad20)") (class "Default")
      (node (ref "U3") (pin "20") (pinfunction "NC_20") (pintype "passive+no_connect"))
    )
    (net (code "133") (name "unconnected-(U3-NC-Pad25)") (class "Default")
      (node (ref "U3") (pin "25") (pinfunction "NC_25") (pintype "passive+no_connect"))
    )
    (net (code "134") (name "unconnected-(U4-NC-Pad7)") (class "Default")
      (node (ref "U4") (pin "7") (pinfunction "NC_7") (pintype "passive+no_connect"))
    )
    (net (code "135") (name "unconnected-(U4-NC-Pad20)") (class "Default")
      (node (ref "U4") (pin "20") (pinfunction "NC_20") (pintype "passive+no_connect"))
    )
    (net (code "136") (name "unconnected-(U4-NC-Pad25)") (class "Default")
      (node (ref "U4") (pin "25") (pinfunction "NC_25") (pintype "passive+no_connect"))
    )
  )
)
